# ems_mbed_rev_a.net
KiCad netlist of a schematic drawn in EAGLE
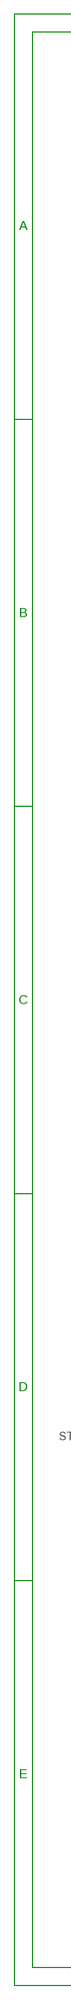
[diagram p0: schematic, sheet 1, part 1 of 2]
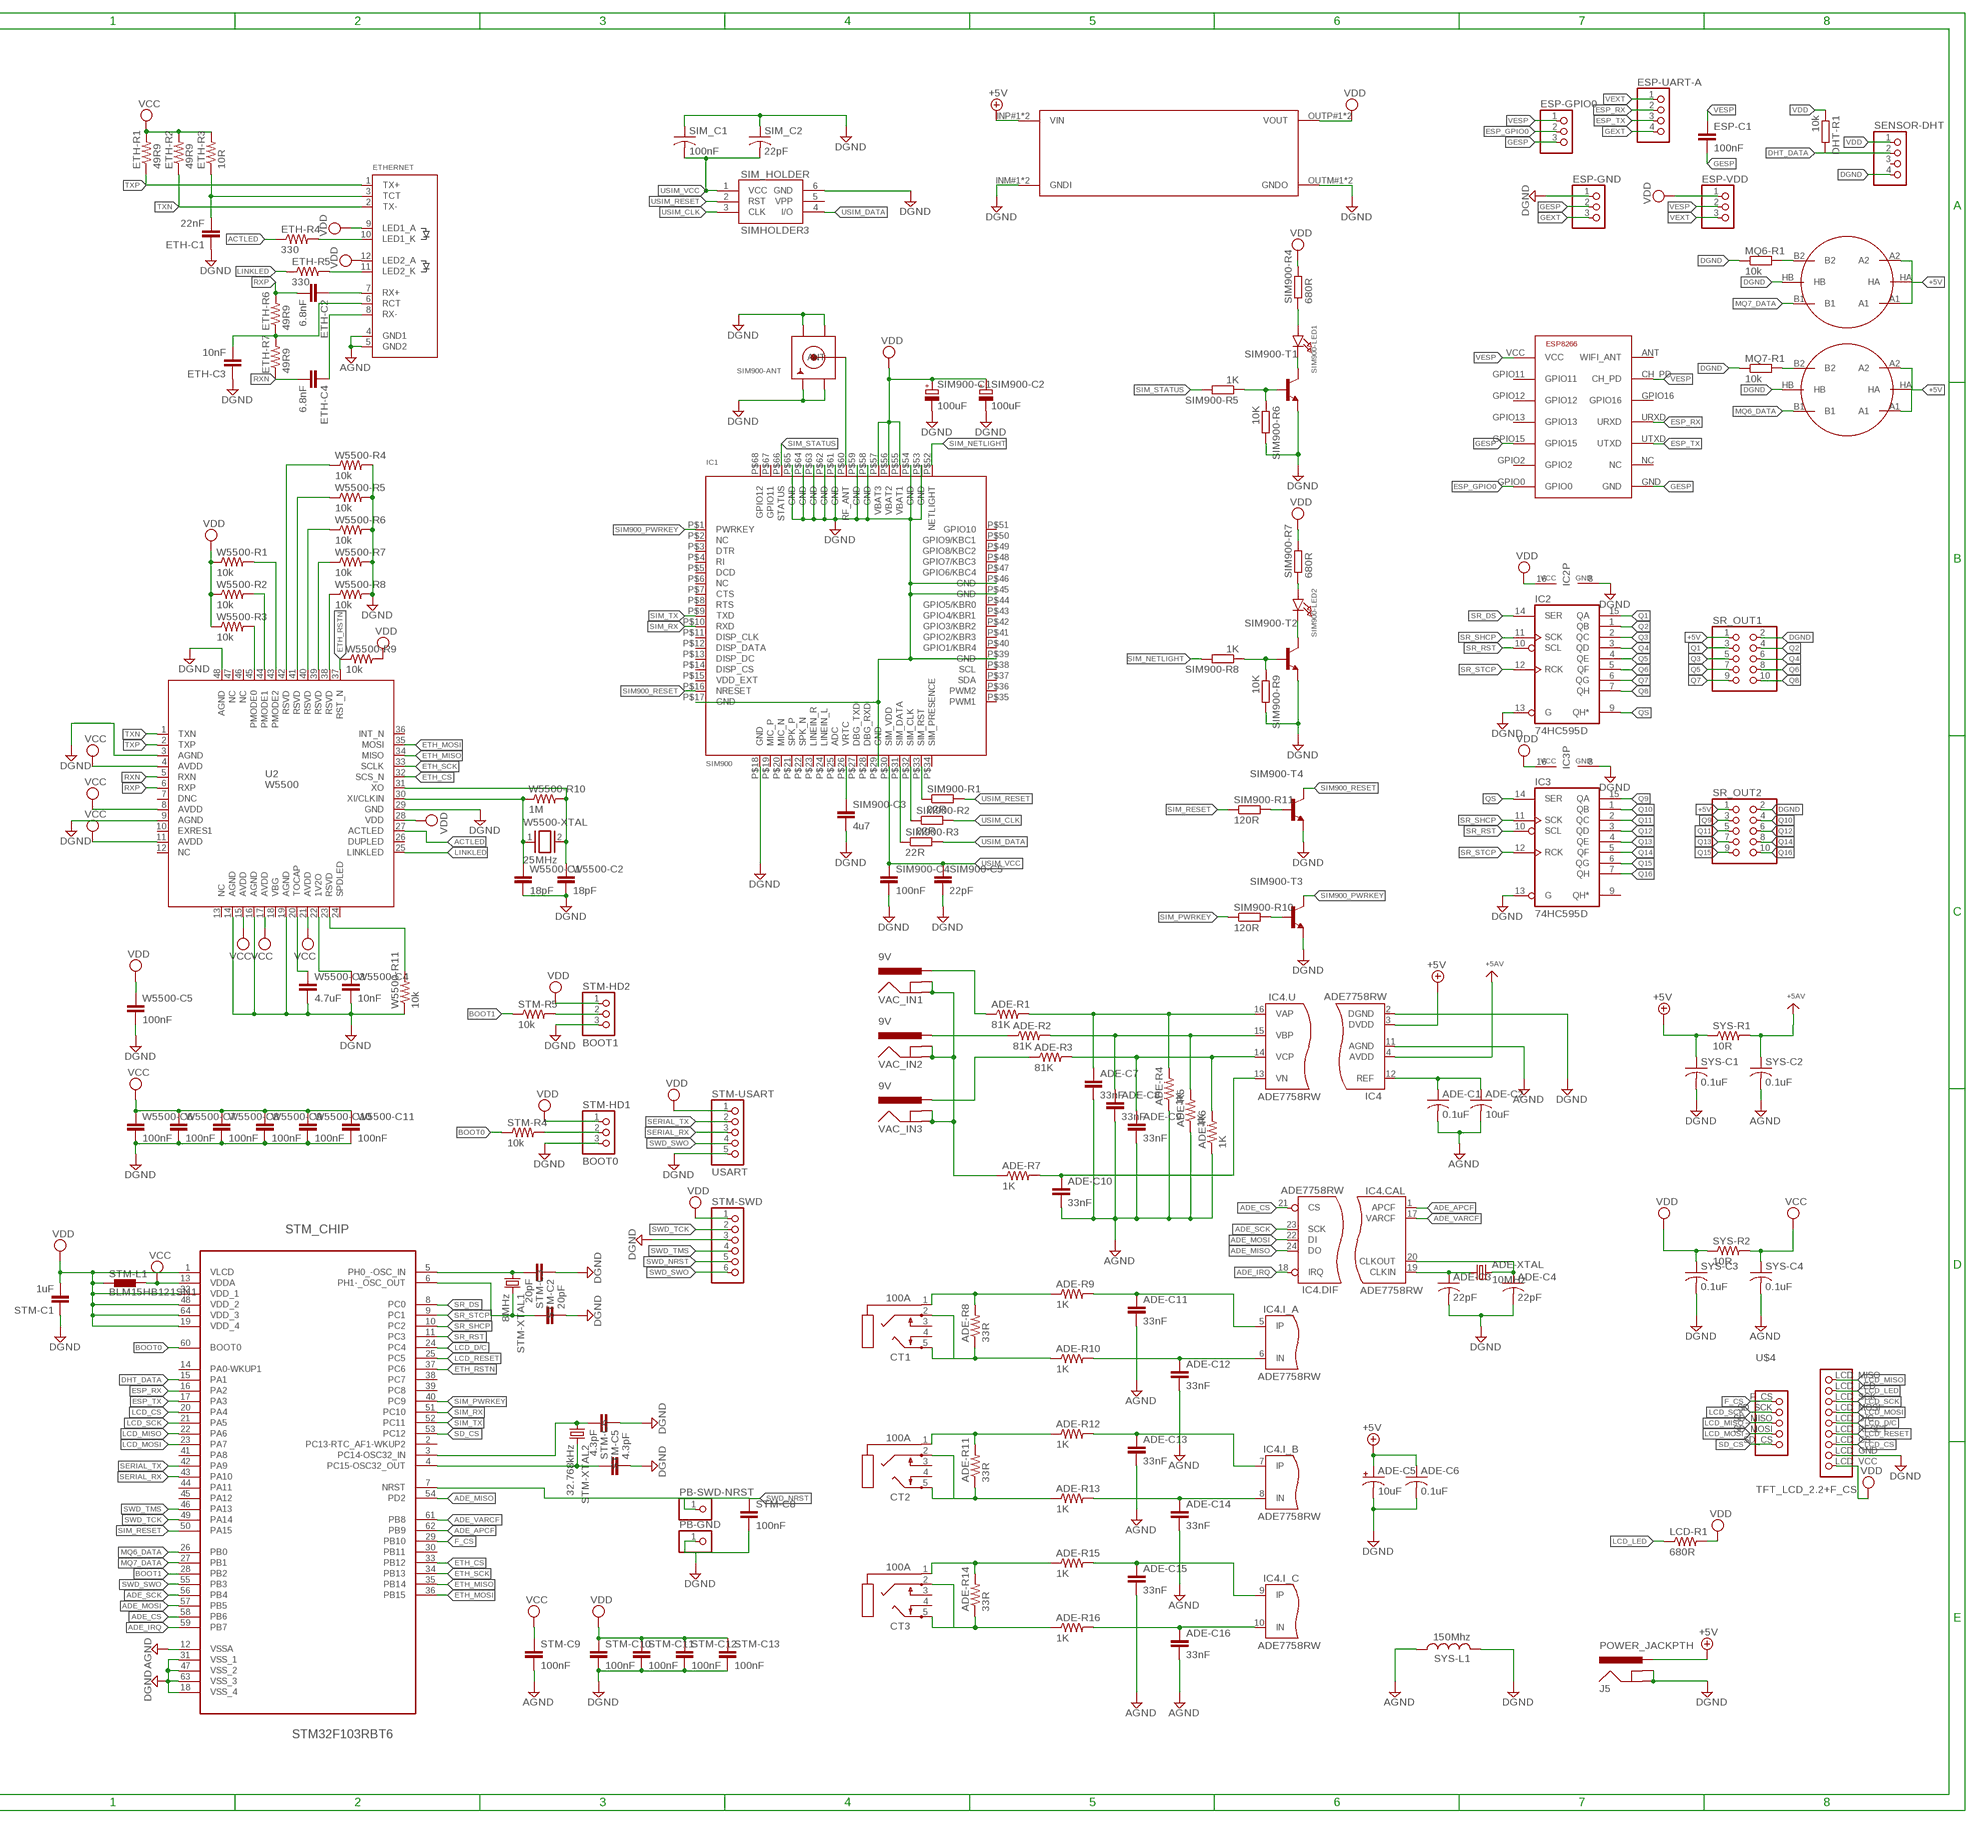
[diagram p1: schematic, sheet 1, part 2 of 2]

(export (version "E")
  (design (tool "Eeschema 10.0.6"))
  (components
    (comp (ref "ADE-C1")
      (value "0.1uF")
      (footprint "eagle-import:C0603@1")
      (libsource (lib "eagle-import") (part "C-USC0603"))
    )
    (comp (ref "ADE-C2")
      (value "10uF")
      (footprint "eagle-import:C0805K")
      (libsource (lib "eagle-import") (part "C-USC0805K"))
    )
    (comp (ref "ADE-C3")
      (value "22pF")
      (footprint "eagle-import:C0603@1")
      (libsource (lib "eagle-import") (part "C-USC0603"))
    )
    (comp (ref "ADE-C4")
      (value "22pF")
      (footprint "eagle-import:C0603")
      (libsource (lib "eagle-import") (part "resistor_C-USC0603"))
    )
    (comp (ref "ADE-C5")
      (value "10uF")
      (footprint "eagle-import:153CLV-0605")
      (libsource (lib "eagle-import") (part "CPOL-US153CLV-0605"))
    )
    (comp (ref "ADE-C6")
      (value "0.1uF")
      (footprint "eagle-import:C0603@1")
      (libsource (lib "eagle-import") (part "C-USC0603"))
    )
    (comp (ref "ADE-C7")
      (value "33nF")
      (footprint "eagle-import:0603-CAP")
      (libsource (lib "eagle-import") (part "CAP0603-CAP"))
    )
    (comp (ref "ADE-C8")
      (value "33nF")
      (footprint "eagle-import:0603-CAP")
      (libsource (lib "eagle-import") (part "CAP0603-CAP"))
    )
    (comp (ref "ADE-C9")
      (value "33nF")
      (footprint "eagle-import:0603-CAP")
      (libsource (lib "eagle-import") (part "CAP0603-CAP"))
    )
    (comp (ref "ADE-C10")
      (value "33nF")
      (footprint "eagle-import:0603-CAP")
      (libsource (lib "eagle-import") (part "CAP0603-CAP"))
    )
    (comp (ref "ADE-C11")
      (value "33nF")
      (footprint "eagle-import:0603-CAP")
      (libsource (lib "eagle-import") (part "CAP0603-CAP"))
    )
    (comp (ref "ADE-C12")
      (value "33nF")
      (footprint "eagle-import:0603-CAP")
      (libsource (lib "eagle-import") (part "CAP0603-CAP"))
    )
    (comp (ref "ADE-C13")
      (value "33nF")
      (footprint "eagle-import:0603-CAP")
      (libsource (lib "eagle-import") (part "CAP0603-CAP"))
    )
    (comp (ref "ADE-C14")
      (value "33nF")
      (footprint "eagle-import:0603-CAP")
      (libsource (lib "eagle-import") (part "CAP0603-CAP"))
    )
    (comp (ref "ADE-C15")
      (value "33nF")
      (footprint "eagle-import:0603-CAP")
      (libsource (lib "eagle-import") (part "CAP0603-CAP"))
    )
    (comp (ref "ADE-C16")
      (value "33nF")
      (footprint "eagle-import:0603-CAP")
      (libsource (lib "eagle-import") (part "CAP0603-CAP"))
    )
    (comp (ref "ADE-R1")
      (value "81K")
      (footprint "eagle-import:0603-RES")
      (libsource (lib "eagle-import") (part "RESISTOR0603-RES"))
    )
    (comp (ref "ADE-R2")
      (value "81K")
      (footprint "eagle-import:0603-RES")
      (libsource (lib "eagle-import") (part "RESISTOR0603-RES"))
    )
    (comp (ref "ADE-R3")
      (value "81K")
      (footprint "eagle-import:0603-RES")
      (libsource (lib "eagle-import") (part "RESISTOR0603-RES"))
    )
    (comp (ref "ADE-R4")
      (value "1K")
      (footprint "eagle-import:0603-RES")
      (libsource (lib "eagle-import") (part "RESISTOR0603-RES"))
    )
    (comp (ref "ADE-R5")
      (value "1K")
      (footprint "eagle-import:0603-RES")
      (libsource (lib "eagle-import") (part "RESISTOR0603-RES"))
    )
    (comp (ref "ADE-R6")
      (value "1K")
      (footprint "eagle-import:0603-RES")
      (libsource (lib "eagle-import") (part "RESISTOR0603-RES"))
    )
    (comp (ref "ADE-R7")
      (value "1K")
      (footprint "eagle-import:0603-RES")
      (libsource (lib "eagle-import") (part "RESISTOR0603-RES"))
    )
    (comp (ref "ADE-R8")
      (value "33R")
      (footprint "eagle-import:0603-RES")
      (libsource (lib "eagle-import") (part "RESISTOR0603-RES"))
    )
    (comp (ref "ADE-R9")
      (value "1K")
      (footprint "eagle-import:0603-RES")
      (libsource (lib "eagle-import") (part "RESISTOR0603-RES"))
    )
    (comp (ref "ADE-R10")
      (value "1K")
      (footprint "eagle-import:0603-RES")
      (libsource (lib "eagle-import") (part "RESISTOR0603-RES"))
    )
    (comp (ref "ADE-R11")
      (value "33R")
      (footprint "eagle-import:0603-RES")
      (libsource (lib "eagle-import") (part "RESISTOR0603-RES"))
    )
    (comp (ref "ADE-R12")
      (value "1K")
      (footprint "eagle-import:0603-RES")
      (libsource (lib "eagle-import") (part "RESISTOR0603-RES"))
    )
    (comp (ref "ADE-R13")
      (value "1K")
      (footprint "eagle-import:0603-RES")
      (libsource (lib "eagle-import") (part "RESISTOR0603-RES"))
    )
    (comp (ref "ADE-R14")
      (value "33R")
      (footprint "eagle-import:0603-RES")
      (libsource (lib "eagle-import") (part "RESISTOR0603-RES"))
    )
    (comp (ref "ADE-R15")
      (value "1K")
      (footprint "eagle-import:0603-RES")
      (libsource (lib "eagle-import") (part "RESISTOR0603-RES"))
    )
    (comp (ref "ADE-R16")
      (value "1K")
      (footprint "eagle-import:0603-RES")
      (libsource (lib "eagle-import") (part "RESISTOR0603-RES"))
    )
    (comp (ref "ADE-XTAL")
      (value "10MHz")
      (footprint "eagle-import:HC49US")
      (libsource (lib "eagle-import") (part "CRYSTALHC49US"))
    )
    (comp (ref "CT1")
      (value "100A")
      (footprint "eagle-import:STX3100")
      (libsource (lib "eagle-import") (part "AUDIO_STEREOJACK"))
    )
    (comp (ref "CT2")
      (value "100A")
      (footprint "eagle-import:STX3100")
      (libsource (lib "eagle-import") (part "AUDIO_STEREOJACK"))
    )
    (comp (ref "CT3")
      (value "100A")
      (footprint "eagle-import:STX3100")
      (libsource (lib "eagle-import") (part "AUDIO_STEREOJACK"))
    )
    (comp (ref "DCDC-3.5V")
      (value "DCDCMODULE_SMALL")
      (footprint "eagle-import:DCDCMODULE-SMALL")
      (libsource (lib "eagle-import") (part "DCDCMODULE_SMALL"))
    )
    (comp (ref "DHT-R1")
      (value "10k")
      (footprint "eagle-import:R0603")
      (libsource (lib "eagle-import") (part "resistor_R-EU_R0603"))
    )
    (comp (ref "ESP-C1")
      (value "100nF")
      (footprint "eagle-import:C0603@1")
      (libsource (lib "eagle-import") (part "C-EUC0603"))
    )
    (comp (ref "ESP-GND")
      (value "PINHD-1X3")
      (footprint "eagle-import:1X03")
      (libsource (lib "eagle-import") (part "PINHD-1X3"))
    )
    (comp (ref "ESP-GPIO0")
      (value "PINHD-1X3")
      (footprint "eagle-import:1X03")
      (libsource (lib "eagle-import") (part "PINHD-1X3"))
    )
    (comp (ref "ESP-UART-A")
      (value "PINHD-1X4")
      (footprint "eagle-import:1X04")
      (libsource (lib "eagle-import") (part "PINHD-1X4"))
    )
    (comp (ref "ESP-VDD")
      (value "PINHD-1X3")
      (footprint "eagle-import:1X03")
      (libsource (lib "eagle-import") (part "PINHD-1X3"))
    )
    (comp (ref "ESP8266")
      (value "ESP-07")
      (footprint "eagle-import:ESP-07")
      (libsource (lib "eagle-import") (part "ESP-07"))
    )
    (comp (ref "ETH-C1")
      (value "22nF")
      (footprint "eagle-import:C0603@1")
      (libsource (lib "eagle-import") (part "C-EUC0603"))
    )
    (comp (ref "ETH-C2")
      (value "6.8nF")
      (footprint "eagle-import:C0603@1")
      (libsource (lib "eagle-import") (part "C-EUC0603"))
    )
    (comp (ref "ETH-C3")
      (value "10nF")
      (footprint "eagle-import:C0603@1")
      (libsource (lib "eagle-import") (part "C-EUC0603"))
    )
    (comp (ref "ETH-C4")
      (value "6.8nF")
      (footprint "eagle-import:C0603@1")
      (libsource (lib "eagle-import") (part "C-EUC0603"))
    )
    (comp (ref "ETH-R1")
      (value "49R9")
      (footprint "eagle-import:R0603")
      (libsource (lib "eagle-import") (part "R-US_R0603"))
    )
    (comp (ref "ETH-R2")
      (value "49R9")
      (footprint "eagle-import:R0603")
      (libsource (lib "eagle-import") (part "R-US_R0603"))
    )
    (comp (ref "ETH-R3")
      (value "10R")
      (footprint "eagle-import:R0603")
      (libsource (lib "eagle-import") (part "R-US_R0603"))
    )
    (comp (ref "ETH-R4")
      (value "330")
      (footprint "eagle-import:R0603")
      (libsource (lib "eagle-import") (part "R-US_R0603"))
    )
    (comp (ref "ETH-R5")
      (value "330")
      (footprint "eagle-import:R0603")
      (libsource (lib "eagle-import") (part "R-US_R0603"))
    )
    (comp (ref "ETH-R6")
      (value "49R9")
      (footprint "eagle-import:R0603")
      (libsource (lib "eagle-import") (part "R-US_R0603"))
    )
    (comp (ref "ETH-R7")
      (value "49R9")
      (footprint "eagle-import:R0603")
      (libsource (lib "eagle-import") (part "R-US_R0603"))
    )
    (comp (ref "ETHERNET")
      (value "RJ45J0026D21BNL")
      (footprint "eagle-import:RJ45_PULSEJACK")
      (libsource (lib "eagle-import") (part "RJ45J0026D21BNL"))
    )
    (comp (ref "IC1")
      (value "SIM900")
      (footprint "eagle-import:SIM900_SMT")
      (libsource (lib "eagle-import") (part "GSM_SIM900_LITERAL"))
    )
    (comp (ref "IC2")
      (value "74HC595D")
      (footprint "eagle-import:SO16")
      (libsource (lib "eagle-import") (part "74595DHC"))
    )
    (comp (ref "IC3")
      (value "74HC595D")
      (footprint "eagle-import:SO16")
      (libsource (lib "eagle-import") (part "74595DHC"))
    )
    (comp (ref "IC4")
      (value "ADE7758RW")
      (footprint "eagle-import:SOIC24")
      (libsource (lib "eagle-import") (part "ADE7758RW"))
    )
    (comp (ref "J5")
      (value "POWER_JACKPTH")
      (footprint "eagle-import:POWER_JACK_PTH")
      (libsource (lib "eagle-import") (part "POWER_JACKPTH"))
    )
    (comp (ref "LCD-R1")
      (value "680R")
      (footprint "eagle-import:0603-RES")
      (libsource (lib "eagle-import") (part "RESISTOR0603-RES"))
    )
    (comp (ref "MQ6-R1")
      (value "10k")
      (footprint "eagle-import:R0603")
      (libsource (lib "eagle-import") (part "resistor_R-EU_R0603"))
    )
    (comp (ref "MQ7-R1")
      (value "10k")
      (footprint "eagle-import:R0603")
      (libsource (lib "eagle-import") (part "resistor_R-EU_R0603"))
    )
    (comp (ref "PB-GND")
      (value "PINHD-1X1CB")
      (footprint "eagle-import:1X01-CLEANBIG")
      (libsource (lib "eagle-import") (part "PINHD-1X1CB"))
    )
    (comp (ref "PB-SWD-NRST")
      (value "PINHD-1X1CB")
      (footprint "eagle-import:1X01-CLEANBIG")
      (libsource (lib "eagle-import") (part "PINHD-1X1CB"))
    )
    (comp (ref "SENSOR-DHT")
      (value "PINHD-1X4")
      (footprint "eagle-import:1X04")
      (libsource (lib "eagle-import") (part "PINHD-1X4"))
    )
    (comp (ref "SENSOR-MQ6")
      (value "METHANE_SENSOR")
      (footprint "eagle-import:MQ-3")
      (libsource (lib "eagle-import") (part "METHANE_SENSOR"))
    )
    (comp (ref "SENSOR-MQ7")
      (value "METHANE_SENSOR")
      (footprint "eagle-import:MQ-3")
      (libsource (lib "eagle-import") (part "METHANE_SENSOR"))
    )
    (comp (ref "SIM900-ANT")
      (value "SMACONNECTOR")
      (footprint "eagle-import:SMA90_DIP")
      (libsource (lib "eagle-import") (part "SMACONNECTOR"))
    )
    (comp (ref "SIM900-C1")
      (value "100uF")
      (footprint "eagle-import:153CLV-0605")
      (libsource (lib "eagle-import") (part "CPOL-EU153CLV-0605"))
    )
    (comp (ref "SIM900-C2")
      (value "100uF")
      (footprint "eagle-import:153CLV-0605")
      (libsource (lib "eagle-import") (part "CPOL-EU153CLV-0605"))
    )
    (comp (ref "SIM900-C3")
      (value "4u7")
      (footprint "eagle-import:C0603@1")
      (libsource (lib "eagle-import") (part "C-EUC0603"))
    )
    (comp (ref "SIM900-C4")
      (value "100nF")
      (footprint "eagle-import:C0603@1")
      (libsource (lib "eagle-import") (part "C-EUC0603"))
    )
    (comp (ref "SIM900-C5")
      (value "22pF")
      (footprint "eagle-import:C0603@1")
      (libsource (lib "eagle-import") (part "C-EUC0603"))
    )
    (comp (ref "SIM900-LED1")
      (value "LED0805_NOOUTLINE")
      (footprint "eagle-import:CHIPLED_0805_NOOUTLINE")
      (libsource (lib "eagle-import") (part "LED0805_NOOUTLINE"))
    )
    (comp (ref "SIM900-LED2")
      (value "LED0805_NOOUTLINE")
      (footprint "eagle-import:CHIPLED_0805_NOOUTLINE")
      (libsource (lib "eagle-import") (part "LED0805_NOOUTLINE"))
    )
    (comp (ref "SIM900-R1")
      (value "22R")
      (footprint "eagle-import:R0603")
      (libsource (lib "eagle-import") (part "R-EU_R0603"))
    )
    (comp (ref "SIM900-R2")
      (value "22R")
      (footprint "eagle-import:R0603")
      (libsource (lib "eagle-import") (part "R-EU_R0603"))
    )
    (comp (ref "SIM900-R3")
      (value "22R")
      (footprint "eagle-import:R0603")
      (libsource (lib "eagle-import") (part "R-EU_R0603"))
    )
    (comp (ref "SIM900-R4")
      (value "680R")
      (footprint "eagle-import:R0603")
      (libsource (lib "eagle-import") (part "R-EU_R0603"))
    )
    (comp (ref "SIM900-R5")
      (value "1K")
      (footprint "eagle-import:R0603")
      (libsource (lib "eagle-import") (part "R-EU_R0603"))
    )
    (comp (ref "SIM900-R6")
      (value "10K")
      (footprint "eagle-import:R0603")
      (libsource (lib "eagle-import") (part "R-EU_R0603"))
    )
    (comp (ref "SIM900-R7")
      (value "680R")
      (footprint "eagle-import:R0603")
      (libsource (lib "eagle-import") (part "R-EU_R0603"))
    )
    (comp (ref "SIM900-R8")
      (value "1K")
      (footprint "eagle-import:R0603")
      (libsource (lib "eagle-import") (part "R-EU_R0603"))
    )
    (comp (ref "SIM900-R9")
      (value "10K")
      (footprint "eagle-import:R0603")
      (libsource (lib "eagle-import") (part "R-EU_R0603"))
    )
    (comp (ref "SIM900-R10")
      (value "120R")
      (footprint "eagle-import:R0603")
      (libsource (lib "eagle-import") (part "resistor_R-EU_R0603"))
    )
    (comp (ref "SIM900-R11")
      (value "120R")
      (footprint "eagle-import:R0603")
      (libsource (lib "eagle-import") (part "resistor_R-EU_R0603"))
    )
    (comp (ref "SIM900-T1")
      (value "MMBT2222ALT1-NPN-SOT23-BEC")
      (footprint "eagle-import:SOT23-BEC")
      (libsource (lib "eagle-import") (part "-NPN-SOT23-BECMMBT2222ALT1"))
    )
    (comp (ref "SIM900-T2")
      (value "MMBT2222ALT1-NPN-SOT23-BEC")
      (footprint "eagle-import:SOT23-BEC")
      (libsource (lib "eagle-import") (part "-NPN-SOT23-BECMMBT2222ALT1"))
    )
    (comp (ref "SIM900-T3")
      (value "MMBT2222ALT1-NPN-SOT23-BEC")
      (footprint "eagle-import:SOT23-BEC")
      (libsource (lib "eagle-import") (part "transistor-neu-to92_-NPN-SOT23-BECMMBT2222ALT1"))
    )
    (comp (ref "SIM900-T4")
      (value "MMBT2222ALT1-NPN-SOT23-BEC")
      (footprint "eagle-import:SOT23-BEC")
      (libsource (lib "eagle-import") (part "transistor-neu-to92_-NPN-SOT23-BECMMBT2222ALT1"))
    )
    (comp (ref "SIM_C1")
      (value "100nF")
      (footprint "eagle-import:C0603K")
      (libsource (lib "eagle-import") (part "C-USC0603K"))
    )
    (comp (ref "SIM_C2")
      (value "22pF")
      (footprint "eagle-import:C0603K")
      (libsource (lib "eagle-import") (part "C-USC0603K"))
    )
    (comp (ref "SIM_HOLDER")
      (value "SIMHOLDER3")
      (footprint "eagle-import:SIMHOLDER3")
      (libsource (lib "eagle-import") (part "SIMHOLDER3"))
    )
    (comp (ref "SR_OUT1")
      (value "PINHD-2X5/90")
      (footprint "eagle-import:2X05_90")
      (libsource (lib "eagle-import") (part "PINHD-2X5/90"))
    )
    (comp (ref "SR_OUT2")
      (value "PINHD-2X5/90")
      (footprint "eagle-import:2X05_90")
      (libsource (lib "eagle-import") (part "PINHD-2X5/90"))
    )
    (comp (ref "STM-C1")
      (value "1uF")
      (footprint "eagle-import:C0603@1")
      (libsource (lib "eagle-import") (part "C-EUC0603"))
    )
    (comp (ref "STM-C2")
      (value "20pF")
      (footprint "eagle-import:C0603@1")
      (libsource (lib "eagle-import") (part "C-EUC0603"))
    )
    (comp (ref "STM-C3")
      (value "20pF")
      (footprint "eagle-import:C0603@1")
      (libsource (lib "eagle-import") (part "C-EUC0603"))
    )
    (comp (ref "STM-C5")
      (value "4.3pF")
      (footprint "eagle-import:C0603@1")
      (libsource (lib "eagle-import") (part "C-EUC0603"))
    )
    (comp (ref "STM-C6")
      (value "4.3pF")
      (footprint "eagle-import:C0603@1")
      (libsource (lib "eagle-import") (part "C-EUC0603"))
    )
    (comp (ref "STM-C8")
      (value "100nF")
      (footprint "eagle-import:C0603@1")
      (libsource (lib "eagle-import") (part "C-EUC0603"))
    )
    (comp (ref "STM-C9")
      (value "100nF")
      (footprint "eagle-import:C0603@1")
      (libsource (lib "eagle-import") (part "C-EUC0603"))
    )
    (comp (ref "STM-C10")
      (value "100nF")
      (footprint "eagle-import:C0603@1")
      (libsource (lib "eagle-import") (part "C-EUC0603"))
    )
    (comp (ref "STM-C11")
      (value "100nF")
      (footprint "eagle-import:C0603@1")
      (libsource (lib "eagle-import") (part "C-EUC0603"))
    )
    (comp (ref "STM-C12")
      (value "100nF")
      (footprint "eagle-import:C0603@1")
      (libsource (lib "eagle-import") (part "C-EUC0603"))
    )
    (comp (ref "STM-C13")
      (value "100nF")
      (footprint "eagle-import:C0603@1")
      (libsource (lib "eagle-import") (part "C-EUC0603"))
    )
    (comp (ref "STM-HD1")
      (value "BOOT0")
      (footprint "eagle-import:1X03")
      (libsource (lib "eagle-import") (part "PINHD-1X3"))
    )
    (comp (ref "STM-HD2")
      (value "BOOT1")
      (footprint "eagle-import:1X03")
      (libsource (lib "eagle-import") (part "PINHD-1X3"))
    )
    (comp (ref "STM-L1")
      (value "BLM15HB121SN1")
      (footprint "eagle-import:0402")
      (libsource (lib "eagle-import") (part "BLM15HB121SN1"))
    )
    (comp (ref "STM-R4")
      (value "10k")
      (footprint "eagle-import:R0603")
      (libsource (lib "eagle-import") (part "R-US_R0603"))
    )
    (comp (ref "STM-R5")
      (value "10k")
      (footprint "eagle-import:R0603")
      (libsource (lib "eagle-import") (part "R-US_R0603"))
    )
    (comp (ref "STM-SWD")
      (value "PINHD-1X6")
      (footprint "eagle-import:1X06")
      (libsource (lib "eagle-import") (part "PINHD-1X6"))
    )
    (comp (ref "STM-USART")
      (value "USART")
      (footprint "eagle-import:PINHD5")
      (libsource (lib "eagle-import") (part "PINHD5"))
    )
    (comp (ref "STM-XTAL1")
      (value "8MHz")
      (footprint "eagle-import:TC26H")
      (libsource (lib "eagle-import") (part "CRYSTALTC26H"))
    )
    (comp (ref "STM-XTAL2")
      (value "32.768kHz")
      (footprint "eagle-import:TC26H")
      (libsource (lib "eagle-import") (part "CRYSTALTC26H"))
    )
    (comp (ref "STM_CHIP")
      (value "STM32F103RBT6")
      (footprint "eagle-import:QFP50P1200X1200X160-64N")
      (fields (field (name "MPN") "STM32L152RBT6"))
      (libsource (lib "eagle-import") (part "STM32L152RBT6"))
    )
    (comp (ref "SYS-C1")
      (value "0.1uF")
      (footprint "eagle-import:C0603@1")
      (libsource (lib "eagle-import") (part "C-USC0603"))
    )
    (comp (ref "SYS-C2")
      (value "0.1uF")
      (footprint "eagle-import:C0603@1")
      (libsource (lib "eagle-import") (part "C-USC0603"))
    )
    (comp (ref "SYS-C3")
      (value "0.1uF")
      (footprint "eagle-import:C0603@1")
      (libsource (lib "eagle-import") (part "C-USC0603"))
    )
    (comp (ref "SYS-C4")
      (value "0.1uF")
      (footprint "eagle-import:C0603@1")
      (libsource (lib "eagle-import") (part "C-USC0603"))
    )
    (comp (ref "SYS-L1")
      (value "150Mhz")
      (footprint "eagle-import:POWER-CHOKE_WE-TPC")
      (libsource (lib "eagle-import") (part "L-USWE-TPC"))
    )
    (comp (ref "SYS-R1")
      (value "10R")
      (footprint "eagle-import:0603-RES")
      (libsource (lib "eagle-import") (part "RESISTOR0603-RES"))
    )
    (comp (ref "SYS-R2")
      (value "10R")
      (footprint "eagle-import:0603-RES")
      (libsource (lib "eagle-import") (part "RESISTOR0603-RES"))
    )
    (comp (ref "U$4")
      (value "TFT_LCD_2.2+F_CS")
      (footprint "eagle-import:TFT_LCD_2.2+F_CS")
      (libsource (lib "eagle-import") (part "TFT_LCD_2.2+F_CS"))
    )
    (comp (ref "U2")
      (value "W5500")
      (footprint "eagle-import:W5500")
      (libsource (lib "eagle-import") (part "W5500"))
    )
    (comp (ref "VAC_IN1")
      (value "9V")
      (footprint "eagle-import:POWER_JACK_PTH")
      (libsource (lib "eagle-import") (part "POWER_JACKPTH"))
    )
    (comp (ref "VAC_IN2")
      (value "9V")
      (footprint "eagle-import:POWER_JACK_PTH")
      (libsource (lib "eagle-import") (part "POWER_JACKPTH"))
    )
    (comp (ref "VAC_IN3")
      (value "9V")
      (footprint "eagle-import:POWER_JACK_PTH")
      (libsource (lib "eagle-import") (part "POWER_JACKPTH"))
    )
    (comp (ref "W5500-C1")
      (value "18pF")
      (footprint "eagle-import:C0603@1")
      (libsource (lib "eagle-import") (part "C-EUC0603"))
    )
    (comp (ref "W5500-C2")
      (value "18pF")
      (footprint "eagle-import:C0603@1")
      (libsource (lib "eagle-import") (part "C-EUC0603"))
    )
    (comp (ref "W5500-C3")
      (value "4.7uF")
      (footprint "eagle-import:C0603@1")
      (libsource (lib "eagle-import") (part "C-EUC0603"))
    )
    (comp (ref "W5500-C4")
      (value "10nF")
      (footprint "eagle-import:C0603@1")
      (libsource (lib "eagle-import") (part "C-EUC0603"))
    )
    (comp (ref "W5500-C5")
      (value "100nF")
      (footprint "eagle-import:C0603@1")
      (libsource (lib "eagle-import") (part "C-EUC0603"))
    )
    (comp (ref "W5500-C6")
      (value "100nF")
      (footprint "eagle-import:C0603@1")
      (libsource (lib "eagle-import") (part "C-EUC0603"))
    )
    (comp (ref "W5500-C7")
      (value "100nF")
      (footprint "eagle-import:C0603@1")
      (libsource (lib "eagle-import") (part "C-EUC0603"))
    )
    (comp (ref "W5500-C8")
      (value "100nF")
      (footprint "eagle-import:C0603@1")
      (libsource (lib "eagle-import") (part "C-EUC0603"))
    )
    (comp (ref "W5500-C9")
      (value "100nF")
      (footprint "eagle-import:C0603@1")
      (libsource (lib "eagle-import") (part "C-EUC0603"))
    )
    (comp (ref "W5500-C10")
      (value "100nF")
      (footprint "eagle-import:C0603@1")
      (libsource (lib "eagle-import") (part "C-EUC0603"))
    )
    (comp (ref "W5500-C11")
      (value "100nF")
      (footprint "eagle-import:C0603@1")
      (libsource (lib "eagle-import") (part "C-EUC0603"))
    )
    (comp (ref "W5500-R1")
      (value "10k")
      (footprint "eagle-import:R0603")
      (libsource (lib "eagle-import") (part "R-US_R0603"))
    )
    (comp (ref "W5500-R2")
      (value "10k")
      (footprint "eagle-import:R0603")
      (libsource (lib "eagle-import") (part "R-US_R0603"))
    )
    (comp (ref "W5500-R3")
      (value "10k")
      (footprint "eagle-import:R0603")
      (libsource (lib "eagle-import") (part "R-US_R0603"))
    )
    (comp (ref "W5500-R4")
      (value "10k")
      (footprint "eagle-import:R0603")
      (libsource (lib "eagle-import") (part "R-US_R0603"))
    )
    (comp (ref "W5500-R5")
      (value "10k")
      (footprint "eagle-import:R0603")
      (libsource (lib "eagle-import") (part "R-US_R0603"))
    )
    (comp (ref "W5500-R6")
      (value "10k")
      (footprint "eagle-import:R0603")
      (libsource (lib "eagle-import") (part "R-US_R0603"))
    )
    (comp (ref "W5500-R7")
      (value "10k")
      (footprint "eagle-import:R0603")
      (libsource (lib "eagle-import") (part "R-US_R0603"))
    )
    (comp (ref "W5500-R8")
      (value "10k")
      (footprint "eagle-import:R0603")
      (libsource (lib "eagle-import") (part "R-US_R0603"))
    )
    (comp (ref "W5500-R9")
      (value "10k")
      (footprint "eagle-import:R0603")
      (libsource (lib "eagle-import") (part "R-US_R0603"))
    )
    (comp (ref "W5500-R10")
      (value "1M")
      (footprint "eagle-import:R0603")
      (libsource (lib "eagle-import") (part "R-US_R0603"))
    )
    (comp (ref "W5500-R11")
      (value "10k")
      (footprint "eagle-import:R0603")
      (libsource (lib "eagle-import") (part "R-US_R0603"))
    )
    (comp (ref "W5500-XTAL")
      (value "25MHz")
      (footprint "eagle-import:QS")
      (libsource (lib "eagle-import") (part "XTAL/S"))
    )
  )
  (nets
    (net (code "1") (name "+5AV") (class "Default")
      (node (ref "IC4") (pin "4") (pinfunction "AVDD_4") (pintype "power_in"))
      (node (ref "SYS-C2") (pin "1") (pinfunction "1_1") (pintype "passive"))
      (node (ref "SYS-R1") (pin "2") (pinfunction "2_2") (pintype "passive"))
    )
    (net (code "2") (name "+5V") (class "Default")
      (node (ref "ADE-C5") (pin "+") (pinfunction "+_+") (pintype "passive"))
      (node (ref "ADE-C6") (pin "1") (pinfunction "1_1") (pintype "passive"))
      (node (ref "DCDC-3.5V") (pin "INP#1") (pinfunction "VIN_INP#1") (pintype "bidirectional"))
      (node (ref "DCDC-3.5V") (pin "INP#2") (pinfunction "VIN_INP#2") (pintype "bidirectional"))
      (node (ref "IC4") (pin "3") (pinfunction "DVDD_3") (pintype "power_in"))
      (node (ref "J5") (pin "PWR") (pinfunction "PWR_PWR") (pintype "bidirectional"))
      (node (ref "SENSOR-MQ6") (pin "A1") (pinfunction "A1_A1") (pintype "bidirectional"))
      (node (ref "SENSOR-MQ6") (pin "A2") (pinfunction "A2_A2") (pintype "bidirectional"))
      (node (ref "SENSOR-MQ6") (pin "HA") (pinfunction "HA_HA") (pintype "bidirectional"))
      (node (ref "SENSOR-MQ7") (pin "A1") (pinfunction "A1_A1") (pintype "bidirectional"))
      (node (ref "SENSOR-MQ7") (pin "A2") (pinfunction "A2_A2") (pintype "bidirectional"))
      (node (ref "SENSOR-MQ7") (pin "HA") (pinfunction "HA_HA") (pintype "bidirectional"))
      (node (ref "SR_OUT1") (pin "1") (pinfunction "1_1") (pintype "passive"))
      (node (ref "SR_OUT2") (pin "1") (pinfunction "1_1") (pintype "passive"))
      (node (ref "SYS-C1") (pin "1") (pinfunction "1_1") (pintype "passive"))
      (node (ref "SYS-R1") (pin "1") (pinfunction "1_1") (pintype "passive"))
    )
    (net (code "3") (name "/GPIO11") (class "Default")
      (node (ref "IC1") (pin "P$67") (pinfunction "GPIO11_P$67") (pintype "power_in"))
    )
    (net (code "4") (name "/GPIO12") (class "Default")
      (node (ref "IC1") (pin "P$68") (pinfunction "GPIO12_P$68") (pintype "power_in"))
    )
    (net (code "5") (name "ACTLED") (class "Default")
      (node (ref "ETH-R4") (pin "1") (pinfunction "1_1") (pintype "passive"))
      (node (ref "U2") (pin "27") (pinfunction "ACTLED_27") (pintype "passive"))
    )
    (net (code "6") (name "ADE_APCF") (class "Default")
      (node (ref "IC4") (pin "1") (pinfunction "APCF_1") (pintype "output"))
      (node (ref "STM_CHIP") (pin "62") (pinfunction "PB9_62") (pintype "bidirectional"))
    )
    (net (code "7") (name "ADE_CS") (class "Default")
      (node (ref "IC4") (pin "21") (pinfunction "CS_21") (pintype "input"))
      (node (ref "STM_CHIP") (pin "58") (pinfunction "PB6_58") (pintype "bidirectional"))
    )
    (net (code "8") (name "ADE_IRQ") (class "Default")
      (node (ref "IC4") (pin "18") (pinfunction "IRQ_18") (pintype "output"))
      (node (ref "STM_CHIP") (pin "59") (pinfunction "PB7_59") (pintype "bidirectional"))
    )
    (net (code "9") (name "ADE_MISO") (class "Default")
      (node (ref "IC4") (pin "24") (pinfunction "DO_24") (pintype "output"))
      (node (ref "STM_CHIP") (pin "54") (pinfunction "PD2_54") (pintype "bidirectional"))
    )
    (net (code "10") (name "ADE_MOSI") (class "Default")
      (node (ref "IC4") (pin "22") (pinfunction "DI_22") (pintype "input"))
      (node (ref "STM_CHIP") (pin "57") (pinfunction "PB5_57") (pintype "bidirectional"))
    )
    (net (code "11") (name "ADE_SCK") (class "Default")
      (node (ref "IC4") (pin "23") (pinfunction "SCK_23") (pintype "input"))
      (node (ref "STM_CHIP") (pin "56") (pinfunction "PB4_56") (pintype "bidirectional"))
    )
    (net (code "12") (name "ADE_VARCF") (class "Default")
      (node (ref "IC4") (pin "17") (pinfunction "VARCF_17") (pintype "output"))
      (node (ref "STM_CHIP") (pin "61") (pinfunction "PB8_61") (pintype "bidirectional"))
    )
    (net (code "13") (name "AGND") (class "Default")
      (node (ref "ADE-C1") (pin "2") (pinfunction "2_2") (pintype "passive"))
      (node (ref "ADE-C10") (pin "2") (pinfunction "2_2") (pintype "passive"))
      (node (ref "ADE-C11") (pin "2") (pinfunction "2_2") (pintype "passive"))
      (node (ref "ADE-C12") (pin "2") (pinfunction "2_2") (pintype "passive"))
      (node (ref "ADE-C13") (pin "2") (pinfunction "2_2") (pintype "passive"))
      (node (ref "ADE-C14") (pin "2") (pinfunction "2_2") (pintype "passive"))
      (node (ref "ADE-C15") (pin "2") (pinfunction "2_2") (pintype "passive"))
      (node (ref "ADE-C16") (pin "2") (pinfunction "2_2") (pintype "passive"))
      (node (ref "ADE-C2") (pin "2") (pinfunction "2_2") (pintype "passive"))
      (node (ref "ADE-C7") (pin "2") (pinfunction "2_2") (pintype "passive"))
      (node (ref "ADE-C8") (pin "2") (pinfunction "2_2") (pintype "passive"))
      (node (ref "ADE-C9") (pin "2") (pinfunction "2_2") (pintype "passive"))
      (node (ref "ADE-R4") (pin "1") (pinfunction "1_1") (pintype "passive"))
      (node (ref "ADE-R5") (pin "1") (pinfunction "1_1") (pintype "passive"))
      (node (ref "ADE-R6") (pin "1") (pinfunction "1_1") (pintype "passive"))
      (node (ref "ETHERNET") (pin "4") (pinfunction "GND1_4") (pintype "bidirectional"))
      (node (ref "ETHERNET") (pin "5") (pinfunction "GND2_5") (pintype "bidirectional"))
      (node (ref "IC4") (pin "11") (pinfunction "AGND_11") (pintype "power_in"))
      (node (ref "STM-C9") (pin "2") (pinfunction "2_2") (pintype "passive"))
      (node (ref "STM_CHIP") (pin "12") (pinfunction "VSSA_12") (pintype "power_in"))
      (node (ref "SYS-C2") (pin "2") (pinfunction "2_2") (pintype "passive"))
      (node (ref "SYS-C4") (pin "2") (pinfunction "2_2") (pintype "passive"))
      (node (ref "SYS-L1") (pin "1") (pinfunction "1_1") (pintype "passive"))
    )
    (net (code "14") (name "BOOT0") (class "Default")
      (node (ref "STM-R4") (pin "1") (pinfunction "1_1") (pintype "passive"))
      (node (ref "STM_CHIP") (pin "60") (pinfunction "BOOT0_60") (pintype "input"))
    )
    (net (code "15") (name "BOOT1") (class "Default")
      (node (ref "STM-R5") (pin "1") (pinfunction "1_1") (pintype "passive"))
      (node (ref "STM_CHIP") (pin "28") (pinfunction "PB2_28") (pintype "bidirectional"))
    )
    (net (code "16") (name "DGND") (class "Default")
      (node (ref "ADE-C3") (pin "2") (pinfunction "2_2") (pintype "passive"))
      (node (ref "ADE-C4") (pin "2") (pinfunction "2_2") (pintype "passive"))
      (node (ref "ADE-C5") (pin "-") (pinfunction "-_-") (pintype "passive"))
      (node (ref "ADE-C6") (pin "2") (pinfunction "2_2") (pintype "passive"))
      (node (ref "DCDC-3.5V") (pin "INM#1") (pinfunction "GNDI_INM#1") (pintype "bidirectional"))
      (node (ref "DCDC-3.5V") (pin "INM#2") (pinfunction "GNDI_INM#2") (pintype "bidirectional"))
      (node (ref "DCDC-3.5V") (pin "OUTM#1") (pinfunction "GNDO_OUTM#1") (pintype "bidirectional"))
      (node (ref "DCDC-3.5V") (pin "OUTM#2") (pinfunction "GNDO_OUTM#2") (pintype "bidirectional"))
      (node (ref "ESP-GND") (pin "1") (pinfunction "1_1") (pintype "passive"))
      (node (ref "ETH-C1") (pin "1") (pinfunction "1_1") (pintype "passive"))
      (node (ref "ETH-C3") (pin "1") (pinfunction "1_1") (pintype "passive"))
      (node (ref "IC1") (pin "P$17") (pinfunction "GND_P$17") (pintype "power_in"))
      (node (ref "IC1") (pin "P$18") (pinfunction "GND_P$18") (pintype "power_in"))
      (node (ref "IC1") (pin "P$29") (pinfunction "GND_P$29") (pintype "power_in"))
      (node (ref "IC1") (pin "P$39") (pinfunction "GND_P$39") (pintype "power_in"))
      (node (ref "IC1") (pin "P$45") (pinfunction "GND_P$45") (pintype "power_in"))
      (node (ref "IC1") (pin "P$46") (pinfunction "GND_P$46") (pintype "power_in"))
      (node (ref "IC1") (pin "P$53") (pinfunction "GND_P$53") (pintype "power_in"))
      (node (ref "IC1") (pin "P$54") (pinfunction "GND_P$54") (pintype "power_in"))
      (node (ref "IC1") (pin "P$58") (pinfunction "GND_P$58") (pintype "power_in"))
      (node (ref "IC1") (pin "P$59") (pinfunction "GND_P$59") (pintype "power_in"))
      (node (ref "IC1") (pin "P$61") (pinfunction "GND_P$61") (pintype "power_in"))
      (node (ref "IC1") (pin "P$62") (pinfunction "GND_P$62") (pintype "power_in"))
      (node (ref "IC1") (pin "P$63") (pinfunction "GND_P$63") (pintype "power_in"))
      (node (ref "IC1") (pin "P$64") (pinfunction "GND_P$64") (pintype "power_in"))
      (node (ref "IC1") (pin "P$65") (pinfunction "GND_P$65") (pintype "power_in"))
      (node (ref "IC2") (pin "13") (pinfunction "G_13") (pintype "input"))
      (node (ref "IC2") (pin "8") (pinfunction "GND_8") (pintype "power_in"))
      (node (ref "IC3") (pin "13") (pinfunction "G_13") (pintype "input"))
      (node (ref "IC3") (pin "8") (pinfunction "GND_8") (pintype "power_in"))
      (node (ref "IC4") (pin "2") (pinfunction "DGND_2") (pintype "power_in"))
      (node (ref "J5") (pin "GND") (pinfunction "GND_GND") (pintype "bidirectional"))
      (node (ref "J5") (pin "GNDBREAK") (pinfunction "GNDBREAK_GNDBREAK") (pintype "bidirectional"))
      (node (ref "MQ6-R1") (pin "1") (pinfunction "1_1") (pintype "passive"))
      (node (ref "MQ7-R1") (pin "1") (pinfunction "1_1") (pintype "passive"))
      (node (ref "PB-GND") (pin "1") (pinfunction "1_1") (pintype "passive"))
      (node (ref "SENSOR-DHT") (pin "4") (pinfunction "4_4") (pintype "passive"))
      (node (ref "SENSOR-MQ6") (pin "HB") (pinfunction "HB_HB") (pintype "bidirectional"))
      (node (ref "SENSOR-MQ7") (pin "HB") (pinfunction "HB_HB") (pintype "bidirectional"))
      (node (ref "SIM900-ANT") (pin "GND1") (pinfunction "GND1_GND1") (pintype "power_in"))
      (node (ref "SIM900-ANT") (pin "GND2") (pinfunction "GND2_GND2") (pintype "power_in"))
      (node (ref "SIM900-ANT") (pin "GND3") (pinfunction "GND3_GND3") (pintype "power_in"))
      (node (ref "SIM900-ANT") (pin "GND4") (pinfunction "GND4_GND4") (pintype "power_in"))
      (node (ref "SIM900-C1") (pin "-") (pinfunction "-_-") (pintype "passive"))
      (node (ref "SIM900-C2") (pin "-") (pinfunction "-_-") (pintype "passive"))
      (node (ref "SIM900-C3") (pin "2") (pinfunction "2_2") (pintype "passive"))
      (node (ref "SIM900-C4") (pin "2") (pinfunction "2_2") (pintype "passive"))
      (node (ref "SIM900-C5") (pin "2") (pinfunction "2_2") (pintype "passive"))
      (node (ref "SIM900-R6") (pin "2") (pinfunction "2_2") (pintype "passive"))
      (node (ref "SIM900-R9") (pin "2") (pinfunction "2_2") (pintype "passive"))
      (node (ref "SIM900-T1") (pin "E") (pinfunction "E_E") (pintype "passive"))
      (node (ref "SIM900-T2") (pin "E") (pinfunction "E_E") (pintype "passive"))
      (node (ref "SIM900-T3") (pin "E") (pinfunction "E_E") (pintype "passive"))
      (node (ref "SIM900-T4") (pin "E") (pinfunction "E_E") (pintype "passive"))
      (node (ref "SIM_C1") (pin "1") (pinfunction "1_1") (pintype "passive"))
      (node (ref "SIM_C2") (pin "1") (pinfunction "1_1") (pintype "passive"))
      (node (ref "SIM_HOLDER") (pin "6") (pinfunction "GND_6") (pintype "bidirectional"))
      (node (ref "SR_OUT1") (pin "2") (pinfunction "2_2") (pintype "passive"))
      (node (ref "SR_OUT2") (pin "2") (pinfunction "2_2") (pintype "passive"))
      (node (ref "STM-C1") (pin "1") (pinfunction "1_1") (pintype "passive"))
      (node (ref "STM-C10") (pin "2") (pinfunction "2_2") (pintype "passive"))
      (node (ref "STM-C11") (pin "2") (pinfunction "2_2") (pintype "passive"))
      (node (ref "STM-C12") (pin "2") (pinfunction "2_2") (pintype "passive"))
      (node (ref "STM-C13") (pin "2") (pinfunction "2_2") (pintype "passive"))
      (node (ref "STM-C2") (pin "1") (pinfunction "1_1") (pintype "passive"))
      (node (ref "STM-C3") (pin "2") (pinfunction "2_2") (pintype "passive"))
      (node (ref "STM-C5") (pin "1") (pinfunction "1_1") (pintype "passive"))
      (node (ref "STM-C6") (pin "2") (pinfunction "2_2") (pintype "passive"))
      (node (ref "STM-C8") (pin "2") (pinfunction "2_2") (pintype "passive"))
      (node (ref "STM-HD1") (pin "3") (pinfunction "3_3") (pintype "passive"))
      (node (ref "STM-HD2") (pin "3") (pinfunction "3_3") (pintype "passive"))
      (node (ref "STM-SWD") (pin "3") (pinfunction "3_3") (pintype "passive"))
      (node (ref "STM-USART") (pin "5") (pinfunction "5_5") (pintype "passive"))
      (node (ref "STM_CHIP") (pin "18") (pinfunction "VSS_4_18") (pintype "power_in"))
      (node (ref "STM_CHIP") (pin "31") (pinfunction "VSS_1_31") (pintype "power_in"))
      (node (ref "STM_CHIP") (pin "47") (pinfunction "VSS_2_47") (pintype "power_in"))
      (node (ref "STM_CHIP") (pin "63") (pinfunction "VSS_3_63") (pintype "power_in"))
      (node (ref "SYS-C1") (pin "2") (pinfunction "2_2") (pintype "passive"))
      (node (ref "SYS-C3") (pin "2") (pinfunction "2_2") (pintype "passive"))
      (node (ref "SYS-L1") (pin "2") (pinfunction "2_2") (pintype "passive"))
      (node (ref "U$4") (pin "LCD_GND") (pinfunction "LCD_GND_LCD_GND") (pintype "passive"))
      (node (ref "U2") (pin "14") (pinfunction "AGND_14") (pintype "passive"))
      (node (ref "U2") (pin "16") (pinfunction "AGND_16") (pintype "passive"))
      (node (ref "U2") (pin "19") (pinfunction "AGND_19") (pintype "passive"))
      (node (ref "U2") (pin "29") (pinfunction "GND_29") (pintype "passive"))
      (node (ref "U2") (pin "3") (pinfunction "AGND_3") (pintype "passive"))
      (node (ref "U2") (pin "48") (pinfunction "AGND_48") (pintype "passive"))
      (node (ref "U2") (pin "9") (pinfunction "AGND_9") (pintype "passive"))
      (node (ref "W5500-C1") (pin "2") (pinfunction "2_2") (pintype "passive"))
      (node (ref "W5500-C10") (pin "2") (pinfunction "2_2") (pintype "passive"))
      (node (ref "W5500-C11") (pin "2") (pinfunction "2_2") (pintype "passive"))
      (node (ref "W5500-C2") (pin "2") (pinfunction "2_2") (pintype "passive"))
      (node (ref "W5500-C3") (pin "2") (pinfunction "2_2") (pintype "passive"))
      (node (ref "W5500-C4") (pin "2") (pinfunction "2_2") (pintype "passive"))
      (node (ref "W5500-C5") (pin "2") (pinfunction "2_2") (pintype "passive"))
      (node (ref "W5500-C6") (pin "2") (pinfunction "2_2") (pintype "passive"))
      (node (ref "W5500-C7") (pin "2") (pinfunction "2_2") (pintype "passive"))
      (node (ref "W5500-C8") (pin "2") (pinfunction "2_2") (pintype "passive"))
      (node (ref "W5500-C9") (pin "2") (pinfunction "2_2") (pintype "passive"))
      (node (ref "W5500-R11") (pin "1") (pinfunction "1_1") (pintype "passive"))
      (node (ref "W5500-R4") (pin "2") (pinfunction "2_2") (pintype "passive"))
      (node (ref "W5500-R5") (pin "2") (pinfunction "2_2") (pintype "passive"))
      (node (ref "W5500-R6") (pin "2") (pinfunction "2_2") (pintype "passive"))
      (node (ref "W5500-R7") (pin "2") (pinfunction "2_2") (pintype "passive"))
      (node (ref "W5500-R8") (pin "2") (pinfunction "2_2") (pintype "passive"))
    )
    (net (code "17") (name "DHT_DATA") (class "Default")
      (node (ref "DHT-R1") (pin "2") (pinfunction "2_2") (pintype "passive"))
      (node (ref "SENSOR-DHT") (pin "2") (pinfunction "2_2") (pintype "passive"))
      (node (ref "STM_CHIP") (pin "15") (pinfunction "PA1_15") (pintype "bidirectional"))
    )
    (net (code "18") (name "ESP_GPIO0") (class "Default")
      (node (ref "ESP-GPIO0") (pin "2") (pinfunction "2_2") (pintype "passive"))
      (node (ref "ESP8266") (pin "GPIO0") (pinfunction "GPIO0_GPIO0") (pintype "bidirectional"))
    )
    (net (code "19") (name "ESP_RX") (class "Default")
      (node (ref "ESP-UART-A") (pin "2") (pinfunction "2_2") (pintype "passive"))
      (node (ref "ESP8266") (pin "URXD") (pinfunction "URXD_URXD") (pintype "bidirectional"))
      (node (ref "STM_CHIP") (pin "16") (pinfunction "PA2_16") (pintype "bidirectional"))
    )
    (net (code "20") (name "ESP_TX") (class "Default")
      (node (ref "ESP-UART-A") (pin "3") (pinfunction "3_3") (pintype "passive"))
      (node (ref "ESP8266") (pin "UTXD") (pinfunction "UTXD_UTXD") (pintype "bidirectional"))
      (node (ref "STM_CHIP") (pin "17") (pinfunction "PA3_17") (pintype "bidirectional"))
    )
    (net (code "21") (name "ETH_CS") (class "Default")
      (node (ref "STM_CHIP") (pin "33") (pinfunction "PB12_33") (pintype "bidirectional"))
      (node (ref "U2") (pin "32") (pinfunction "SCS_N_32") (pintype "passive"))
    )
    (net (code "22") (name "ETH_MISO") (class "Default")
      (node (ref "STM_CHIP") (pin "35") (pinfunction "PB14_35") (pintype "bidirectional"))
      (node (ref "U2") (pin "34") (pinfunction "MISO_34") (pintype "passive"))
    )
    (net (code "23") (name "ETH_MOSI") (class "Default")
      (node (ref "STM_CHIP") (pin "36") (pinfunction "PB15_36") (pintype "bidirectional"))
      (node (ref "U2") (pin "35") (pinfunction "MOSI_35") (pintype "passive"))
    )
    (net (code "24") (name "ETH_RSTN") (class "Default")
      (node (ref "STM_CHIP") (pin "37") (pinfunction "PC6_37") (pintype "bidirectional"))
      (node (ref "U2") (pin "37") (pinfunction "RST_N_37") (pintype "passive"))
      (node (ref "W5500-R9") (pin "1") (pinfunction "1_1") (pintype "passive"))
    )
    (net (code "25") (name "ETH_SCK") (class "Default")
      (node (ref "STM_CHIP") (pin "34") (pinfunction "PB13_34") (pintype "bidirectional"))
      (node (ref "U2") (pin "33") (pinfunction "SCLK_33") (pintype "passive"))
    )
    (net (code "26") (name "F_CS") (class "Default")
      (node (ref "STM_CHIP") (pin "29") (pinfunction "PB10_29") (pintype "bidirectional"))
      (node (ref "U$4") (pin "F_CS") (pinfunction "F_CS_F_CS") (pintype "passive"))
    )
    (net (code "27") (name "GESP") (class "Default")
      (node (ref "ESP-C1") (pin "2") (pinfunction "2_2") (pintype "passive"))
      (node (ref "ESP-GND") (pin "2") (pinfunction "2_2") (pintype "passive"))
      (node (ref "ESP-GPIO0") (pin "3") (pinfunction "3_3") (pintype "passive"))
      (node (ref "ESP8266") (pin "GND") (pinfunction "GND_GND") (pintype "bidirectional"))
      (node (ref "ESP8266") (pin "GPIO15") (pinfunction "GPIO15_GPIO15") (pintype "bidirectional"))
    )
    (net (code "28") (name "GEXT") (class "Default")
      (node (ref "ESP-GND") (pin "3") (pinfunction "3_3") (pintype "passive"))
      (node (ref "ESP-UART-A") (pin "4") (pinfunction "4_4") (pintype "passive"))
    )
    (net (code "29") (name "LCD_CS") (class "Default")
      (node (ref "STM_CHIP") (pin "20") (pinfunction "PA4_20") (pintype "bidirectional"))
      (node (ref "U$4") (pin "LCD_CS") (pinfunction "LCD_CS_LCD_CS") (pintype "passive"))
    )
    (net (code "30") (name "LCD_D{slash}C") (class "Default")
      (node (ref "STM_CHIP") (pin "24") (pinfunction "PC4_24") (pintype "bidirectional"))
      (node (ref "U$4") (pin "LCD_D/C") (pinfunction "LCD_D/C_LCD_D/C") (pintype "passive"))
    )
    (net (code "31") (name "LCD_LED") (class "Default")
      (node (ref "LCD-R1") (pin "1") (pinfunction "1_1") (pintype "passive"))
      (node (ref "U$4") (pin "LCD_LED") (pinfunction "LCD_LED_LCD_LED") (pintype "passive"))
    )
    (net (code "32") (name "LCD_MISO") (class "Default")
      (node (ref "STM_CHIP") (pin "22") (pinfunction "PA6_22") (pintype "bidirectional"))
      (node (ref "U$4") (pin "LCD_MISO") (pinfunction "LCD_MISO_LCD_MISO") (pintype "passive"))
      (node (ref "U$4") (pin "SD_MISO") (pinfunction "SD_MISO_SD_MISO") (pintype "passive"))
    )
    (net (code "33") (name "LCD_MOSI") (class "Default")
      (node (ref "STM_CHIP") (pin "23") (pinfunction "PA7_23") (pintype "bidirectional"))
      (node (ref "U$4") (pin "LCD_MOSI") (pinfunction "LCD_MOSI_LCD_MOSI") (pintype "passive"))
      (node (ref "U$4") (pin "SD_MOSI") (pinfunction "SD_MOSI_SD_MOSI") (pintype "passive"))
    )
    (net (code "34") (name "LCD_RESET") (class "Default")
      (node (ref "STM_CHIP") (pin "25") (pinfunction "PC5_25") (pintype "bidirectional"))
      (node (ref "U$4") (pin "LCD_RESET") (pinfunction "LCD_RESET_LCD_RESET") (pintype "passive"))
    )
    (net (code "35") (name "LCD_SCK") (class "Default")
      (node (ref "STM_CHIP") (pin "21") (pinfunction "PA5_21") (pintype "bidirectional"))
      (node (ref "U$4") (pin "LCD_SCK") (pinfunction "LCD_SCK_LCD_SCK") (pintype "passive"))
      (node (ref "U$4") (pin "SD_SCK") (pinfunction "SD_SCK_SD_SCK") (pintype "passive"))
    )
    (net (code "36") (name "LINKLED") (class "Default")
      (node (ref "ETH-R5") (pin "1") (pinfunction "1_1") (pintype "passive"))
      (node (ref "U2") (pin "25") (pinfunction "LINKLED_25") (pintype "passive"))
    )
    (net (code "37") (name "MQ6_DATA") (class "Default")
      (node (ref "SENSOR-MQ7") (pin "B1") (pinfunction "B1_B1") (pintype "bidirectional"))
      (node (ref "STM_CHIP") (pin "26") (pinfunction "PB0_26") (pintype "bidirectional"))
    )
    (net (code "38") (name "MQ7_DATA") (class "Default")
      (node (ref "SENSOR-MQ6") (pin "B1") (pinfunction "B1_B1") (pintype "bidirectional"))
      (node (ref "STM_CHIP") (pin "27") (pinfunction "PB1_27") (pintype "bidirectional"))
    )
    (net (code "39") (name "Net-(ADE-R1-Pad1)") (class "Default")
      (node (ref "ADE-R1") (pin "1") (pinfunction "1_1") (pintype "passive"))
      (node (ref "VAC_IN1") (pin "PWR") (pinfunction "PWR_PWR") (pintype "bidirectional"))
    )
    (net (code "40") (name "Net-(ADE-R2-Pad1)") (class "Default")
      (node (ref "ADE-R2") (pin "1") (pinfunction "1_1") (pintype "passive"))
      (node (ref "VAC_IN2") (pin "PWR") (pinfunction "PWR_PWR") (pintype "bidirectional"))
    )
    (net (code "41") (name "Net-(ADE-R3-Pad1)") (class "Default")
      (node (ref "ADE-R3") (pin "1") (pinfunction "1_1") (pintype "passive"))
      (node (ref "VAC_IN3") (pin "PWR") (pinfunction "PWR_PWR") (pintype "bidirectional"))
    )
    (net (code "42") (name "Net-(ADE-R7-Pad1)") (class "Default")
      (node (ref "ADE-R7") (pin "1") (pinfunction "1_1") (pintype "passive"))
      (node (ref "VAC_IN1") (pin "GND") (pinfunction "GND_GND") (pintype "bidirectional"))
      (node (ref "VAC_IN1") (pin "GNDBREAK") (pinfunction "GNDBREAK_GNDBREAK") (pintype "bidirectional"))
      (node (ref "VAC_IN2") (pin "GND") (pinfunction "GND_GND") (pintype "bidirectional"))
      (node (ref "VAC_IN2") (pin "GNDBREAK") (pinfunction "GNDBREAK_GNDBREAK") (pintype "bidirectional"))
      (node (ref "VAC_IN3") (pin "GND") (pinfunction "GND_GND") (pintype "bidirectional"))
      (node (ref "VAC_IN3") (pin "GNDBREAK") (pinfunction "GNDBREAK_GNDBREAK") (pintype "bidirectional"))
    )
    (net (code "43") (name "Net-(ADE-R8-Pad2)") (class "Default")
      (node (ref "ADE-R8") (pin "2") (pinfunction "2_2") (pintype "passive"))
      (node (ref "ADE-R9") (pin "1") (pinfunction "1_1") (pintype "passive"))
      (node (ref "CT1") (pin "1") (pinfunction "1_1") (pintype "passive"))
    )
    (net (code "44") (name "Net-(ADE-R10-Pad1)") (class "Default")
      (node (ref "ADE-R10") (pin "1") (pinfunction "1_1") (pintype "passive"))
      (node (ref "ADE-R8") (pin "1") (pinfunction "1_1") (pintype "passive"))
      (node (ref "CT1") (pin "2") (pinfunction "2_2") (pintype "passive"))
      (node (ref "CT1") (pin "5") (pinfunction "5_5") (pintype "passive"))
    )
    (net (code "45") (name "Net-(ADE-R11-Pad1)") (class "Default")
      (node (ref "ADE-R11") (pin "1") (pinfunction "1_1") (pintype "passive"))
      (node (ref "ADE-R13") (pin "1") (pinfunction "1_1") (pintype "passive"))
      (node (ref "CT2") (pin "2") (pinfunction "2_2") (pintype "passive"))
      (node (ref "CT2") (pin "5") (pinfunction "5_5") (pintype "passive"))
    )
    (net (code "46") (name "Net-(ADE-R11-Pad2)") (class "Default")
      (node (ref "ADE-R11") (pin "2") (pinfunction "2_2") (pintype "passive"))
      (node (ref "ADE-R12") (pin "1") (pinfunction "1_1") (pintype "passive"))
      (node (ref "CT2") (pin "1") (pinfunction "1_1") (pintype "passive"))
    )
    (net (code "47") (name "Net-(ADE-R14-Pad1)") (class "Default")
      (node (ref "ADE-R14") (pin "1") (pinfunction "1_1") (pintype "passive"))
      (node (ref "ADE-R16") (pin "1") (pinfunction "1_1") (pintype "passive"))
      (node (ref "CT3") (pin "2") (pinfunction "2_2") (pintype "passive"))
      (node (ref "CT3") (pin "5") (pinfunction "5_5") (pintype "passive"))
    )
    (net (code "48") (name "Net-(ADE-R14-Pad2)") (class "Default")
      (node (ref "ADE-R14") (pin "2") (pinfunction "2_2") (pintype "passive"))
      (node (ref "ADE-R15") (pin "1") (pinfunction "1_1") (pintype "passive"))
      (node (ref "CT3") (pin "1") (pinfunction "1_1") (pintype "passive"))
    )
    (net (code "49") (name "Net-(ETHERNET-LED1_K)") (class "Default")
      (node (ref "ETH-R4") (pin "2") (pinfunction "2_2") (pintype "passive"))
      (node (ref "ETHERNET") (pin "10") (pinfunction "LED1_K_10") (pintype "bidirectional"))
    )
    (net (code "50") (name "Net-(ETHERNET-LED2_K)") (class "Default")
      (node (ref "ETH-R5") (pin "2") (pinfunction "2_2") (pintype "passive"))
      (node (ref "ETHERNET") (pin "11") (pinfunction "LED2_K_11") (pintype "bidirectional"))
    )
    (net (code "51") (name "Net-(ETHERNET-RCT)") (class "Default")
      (node (ref "ETH-C3") (pin "2") (pinfunction "2_2") (pintype "passive"))
      (node (ref "ETH-R6") (pin "1") (pinfunction "1_1") (pintype "passive"))
      (node (ref "ETH-R7") (pin "2") (pinfunction "2_2") (pintype "passive"))
      (node (ref "ETHERNET") (pin "6") (pinfunction "RCT_6") (pintype "bidirectional"))
    )
    (net (code "52") (name "Net-(ETHERNET-RX+)") (class "Default")
      (node (ref "ETH-C2") (pin "1") (pinfunction "1_1") (pintype "passive"))
      (node (ref "ETHERNET") (pin "7") (pinfunction "RX+_7") (pintype "bidirectional"))
    )
    (net (code "53") (name "Net-(ETHERNET-RX-)") (class "Default")
      (node (ref "ETH-C4") (pin "1") (pinfunction "1_1") (pintype "passive"))
      (node (ref "ETHERNET") (pin "8") (pinfunction "RX-_8") (pintype "bidirectional"))
    )
    (net (code "54") (name "Net-(ETHERNET-TCT)") (class "Default")
      (node (ref "ETH-C1") (pin "2") (pinfunction "2_2") (pintype "passive"))
      (node (ref "ETH-R3") (pin "1") (pinfunction "1_1") (pintype "passive"))
      (node (ref "ETHERNET") (pin "3") (pinfunction "TCT_3") (pintype "bidirectional"))
    )
    (net (code "55") (name "Net-(IC1-RF_ANT)") (class "Default")
      (node (ref "IC1") (pin "P$60") (pinfunction "RF_ANT_P$60") (pintype "bidirectional"))
      (node (ref "SIM900-ANT") (pin "ANTENNA") (pinfunction "ANT_ANTENNA") (pintype "bidirectional"))
    )
    (net (code "56") (name "Net-(IC1-SIM_CLK)") (class "Default")
      (node (ref "IC1") (pin "P$32") (pinfunction "SIM_CLK_P$32") (pintype "bidirectional"))
      (node (ref "SIM900-R2") (pin "1") (pinfunction "1_1") (pintype "passive"))
    )
    (net (code "57") (name "Net-(IC1-SIM_DATA)") (class "Default")
      (node (ref "IC1") (pin "P$31") (pinfunction "SIM_DATA_P$31") (pintype "bidirectional"))
      (node (ref "SIM900-R3") (pin "1") (pinfunction "1_1") (pintype "passive"))
    )
    (net (code "58") (name "Net-(IC1-SIM_RST)") (class "Default")
      (node (ref "IC1") (pin "P$33") (pinfunction "SIM_RST_P$33") (pintype "bidirectional"))
      (node (ref "SIM900-R1") (pin "1") (pinfunction "1_1") (pintype "passive"))
    )
    (net (code "59") (name "Net-(IC1-VRTC)") (class "Default")
      (node (ref "IC1") (pin "P$26") (pinfunction "VRTC_P$26") (pintype "power_in"))
      (node (ref "SIM900-C3") (pin "1") (pinfunction "1_1") (pintype "passive"))
    )
    (net (code "60") (name "Net-(IC4A-CLKIN)") (class "Default")
      (node (ref "ADE-C3") (pin "1") (pinfunction "1_1") (pintype "passive"))
      (node (ref "ADE-XTAL") (pin "1") (pinfunction "1_1") (pintype "passive"))
      (node (ref "IC4") (pin "19") (pinfunction "CLKIN_19") (pintype "input"))
    )
    (net (code "61") (name "Net-(IC4A-CLKOUT)") (class "Default")
      (node (ref "ADE-C4") (pin "1") (pinfunction "1_1") (pintype "passive"))
      (node (ref "ADE-XTAL") (pin "2") (pinfunction "2_2") (pintype "passive"))
      (node (ref "IC4") (pin "20") (pinfunction "CLKOUT_20") (pintype "output"))
    )
    (net (code "62") (name "Net-(IC4C-IN)") (class "Default")
      (node (ref "ADE-C12") (pin "1") (pinfunction "1_1") (pintype "passive"))
      (node (ref "ADE-R10") (pin "2") (pinfunction "2_2") (pintype "passive"))
      (node (ref "IC4") (pin "6") (pinfunction "IN_6") (pintype "input"))
    )
    (net (code "63") (name "Net-(IC4C-IP)") (class "Default")
      (node (ref "ADE-C11") (pin "1") (pinfunction "1_1") (pintype "passive"))
      (node (ref "ADE-R9") (pin "2") (pinfunction "2_2") (pintype "passive"))
      (node (ref "IC4") (pin "5") (pinfunction "IP_5") (pintype "input"))
    )
    (net (code "64") (name "Net-(IC4D-IN)") (class "Default")
      (node (ref "ADE-C14") (pin "1") (pinfunction "1_1") (pintype "passive"))
      (node (ref "ADE-R13") (pin "2") (pinfunction "2_2") (pintype "passive"))
      (node (ref "IC4") (pin "8") (pinfunction "IN_8") (pintype "input"))
    )
    (net (code "65") (name "Net-(IC4D-IP)") (class "Default")
      (node (ref "ADE-C13") (pin "1") (pinfunction "1_1") (pintype "passive"))
      (node (ref "ADE-R12") (pin "2") (pinfunction "2_2") (pintype "passive"))
      (node (ref "IC4") (pin "7") (pinfunction "IP_7") (pintype "input"))
    )
    (net (code "66") (name "Net-(IC4E-IN)") (class "Default")
      (node (ref "ADE-C16") (pin "1") (pinfunction "1_1") (pintype "passive"))
      (node (ref "ADE-R16") (pin "2") (pinfunction "2_2") (pintype "passive"))
      (node (ref "IC4") (pin "10") (pinfunction "IN_10") (pintype "input"))
    )
    (net (code "67") (name "Net-(IC4E-IP)") (class "Default")
      (node (ref "ADE-C15") (pin "1") (pinfunction "1_1") (pintype "passive"))
      (node (ref "ADE-R15") (pin "2") (pinfunction "2_2") (pintype "passive"))
      (node (ref "IC4") (pin "9") (pinfunction "IP_9") (pintype "input"))
    )
    (net (code "68") (name "Net-(IC4F-REF)") (class "Default")
      (node (ref "ADE-C1") (pin "1") (pinfunction "1_1") (pintype "passive"))
      (node (ref "ADE-C2") (pin "1") (pinfunction "1_1") (pintype "passive"))
      (node (ref "IC4") (pin "12") (pinfunction "REF_12") (pintype "bidirectional"))
    )
    (net (code "69") (name "Net-(IC4G-VAP)") (class "Default")
      (node (ref "ADE-C7") (pin "1") (pinfunction "1_1") (pintype "passive"))
      (node (ref "ADE-R1") (pin "2") (pinfunction "2_2") (pintype "passive"))
      (node (ref "ADE-R4") (pin "2") (pinfunction "2_2") (pintype "passive"))
      (node (ref "IC4") (pin "16") (pinfunction "VAP_16") (pintype "input"))
    )
    (net (code "70") (name "Net-(IC4G-VBP)") (class "Default")
      (node (ref "ADE-C8") (pin "1") (pinfunction "1_1") (pintype "passive"))
      (node (ref "ADE-R2") (pin "2") (pinfunction "2_2") (pintype "passive"))
      (node (ref "ADE-R5") (pin "2") (pinfunction "2_2") (pintype "passive"))
      (node (ref "IC4") (pin "15") (pinfunction "VBP_15") (pintype "input"))
    )
    (net (code "71") (name "Net-(IC4G-VCP)") (class "Default")
      (node (ref "ADE-C9") (pin "1") (pinfunction "1_1") (pintype "passive"))
      (node (ref "ADE-R3") (pin "2") (pinfunction "2_2") (pintype "passive"))
      (node (ref "ADE-R6") (pin "2") (pinfunction "2_2") (pintype "passive"))
      (node (ref "IC4") (pin "14") (pinfunction "VCP_14") (pintype "input"))
    )
    (net (code "72") (name "Net-(IC4G-VN)") (class "Default")
      (node (ref "ADE-C10") (pin "1") (pinfunction "1_1") (pintype "passive"))
      (node (ref "ADE-R7") (pin "2") (pinfunction "2_2") (pintype "passive"))
      (node (ref "IC4") (pin "13") (pinfunction "VN_13") (pintype "input"))
    )
    (net (code "73") (name "Net-(MQ6-R1-Pad2)") (class "Default")
      (node (ref "MQ6-R1") (pin "2") (pinfunction "2_2") (pintype "passive"))
      (node (ref "SENSOR-MQ6") (pin "B2") (pinfunction "B2_B2") (pintype "bidirectional"))
    )
    (net (code "74") (name "Net-(MQ7-R1-Pad2)") (class "Default")
      (node (ref "MQ7-R1") (pin "2") (pinfunction "2_2") (pintype "passive"))
      (node (ref "SENSOR-MQ7") (pin "B2") (pinfunction "B2_B2") (pintype "bidirectional"))
    )
    (net (code "75") (name "Net-(SIM900-LED1-PadA)") (class "Default")
      (node (ref "SIM900-LED1") (pin "A") (pinfunction "A_A") (pintype "passive"))
      (node (ref "SIM900-R4") (pin "1") (pinfunction "1_1") (pintype "passive"))
    )
    (net (code "76") (name "Net-(SIM900-LED1-PadC)") (class "Default")
      (node (ref "SIM900-LED1") (pin "C") (pinfunction "C_C") (pintype "passive"))
      (node (ref "SIM900-T1") (pin "C") (pinfunction "C_C") (pintype "passive"))
    )
    (net (code "77") (name "Net-(SIM900-LED2-PadA)") (class "Default")
      (node (ref "SIM900-LED2") (pin "A") (pinfunction "A_A") (pintype "passive"))
      (node (ref "SIM900-R7") (pin "1") (pinfunction "1_1") (pintype "passive"))
    )
    (net (code "78") (name "Net-(SIM900-LED2-PadC)") (class "Default")
      (node (ref "SIM900-LED2") (pin "C") (pinfunction "C_C") (pintype "passive"))
      (node (ref "SIM900-T2") (pin "C") (pinfunction "C_C") (pintype "passive"))
    )
    (net (code "79") (name "Net-(SIM900-R5-Pad1)") (class "Default")
      (node (ref "SIM900-R5") (pin "1") (pinfunction "1_1") (pintype "passive"))
      (node (ref "SIM900-R6") (pin "1") (pinfunction "1_1") (pintype "passive"))
      (node (ref "SIM900-T1") (pin "B") (pinfunction "B_B") (pintype "passive"))
    )
    (net (code "80") (name "Net-(SIM900-R8-Pad1)") (class "Default")
      (node (ref "SIM900-R8") (pin "1") (pinfunction "1_1") (pintype "passive"))
      (node (ref "SIM900-R9") (pin "1") (pinfunction "1_1") (pintype "passive"))
      (node (ref "SIM900-T2") (pin "B") (pinfunction "B_B") (pintype "passive"))
    )
    (net (code "81") (name "Net-(SIM900-R10-Pad2)") (class "Default")
      (node (ref "SIM900-R10") (pin "2") (pinfunction "2_2") (pintype "passive"))
      (node (ref "SIM900-T3") (pin "B") (pinfunction "B_B") (pintype "passive"))
    )
    (net (code "82") (name "Net-(SIM900-R11-Pad2)") (class "Default")
      (node (ref "SIM900-R11") (pin "2") (pinfunction "2_2") (pintype "passive"))
      (node (ref "SIM900-T4") (pin "B") (pinfunction "B_B") (pintype "passive"))
    )
    (net (code "83") (name "Net-(STM-HD1-Pad2)") (class "Default")
      (node (ref "STM-HD1") (pin "2") (pinfunction "2_2") (pintype "passive"))
      (node (ref "STM-R4") (pin "2") (pinfunction "2_2") (pintype "passive"))
    )
    (net (code "84") (name "Net-(STM-HD2-Pad2)") (class "Default")
      (node (ref "STM-HD2") (pin "2") (pinfunction "2_2") (pintype "passive"))
      (node (ref "STM-R5") (pin "2") (pinfunction "2_2") (pintype "passive"))
    )
    (net (code "85") (name "Net-(STM_CHIP-PC14-OSC32_IN)") (class "Default")
      (node (ref "STM-C5") (pin "2") (pinfunction "2_2") (pintype "passive"))
      (node (ref "STM-XTAL2") (pin "1") (pinfunction "1_1") (pintype "passive"))
      (node (ref "STM_CHIP") (pin "3") (pinfunction "PC14-OSC32_IN_3") (pintype "bidirectional"))
    )
    (net (code "86") (name "Net-(STM_CHIP-PC15-OSC32_OUT)") (class "Default")
      (node (ref "STM-C6") (pin "1") (pinfunction "1_1") (pintype "passive"))
      (node (ref "STM-XTAL2") (pin "2") (pinfunction "2_2") (pintype "passive"))
      (node (ref "STM_CHIP") (pin "4") (pinfunction "PC15-OSC32_OUT_4") (pintype "bidirectional"))
    )
    (net (code "87") (name "Net-(STM_CHIP-PH0_-OSC_IN)") (class "Default")
      (node (ref "STM-C2") (pin "2") (pinfunction "2_2") (pintype "passive"))
      (node (ref "STM-XTAL1") (pin "1") (pinfunction "1_1") (pintype "passive"))
      (node (ref "STM_CHIP") (pin "5") (pinfunction "PH0_-OSC_IN_5") (pintype "bidirectional"))
    )
    (net (code "88") (name "Net-(STM_CHIP-PH1-_OSC_OUT)") (class "Default")
      (node (ref "STM-C3") (pin "1") (pinfunction "1_1") (pintype "passive"))
      (node (ref "STM-XTAL1") (pin "2") (pinfunction "2_2") (pintype "passive"))
      (node (ref "STM_CHIP") (pin "6") (pinfunction "PH1-_OSC_OUT_6") (pintype "bidirectional"))
    )
    (net (code "89") (name "Net-(U2-1V2O)") (class "Default")
      (node (ref "U2") (pin "22") (pinfunction "1V2O_22") (pintype "passive"))
      (node (ref "W5500-C4") (pin "1") (pinfunction "1_1") (pintype "passive"))
    )
    (net (code "90") (name "Net-(U2-PMODE0)") (class "Default")
      (node (ref "U2") (pin "45") (pinfunction "PMODE0_45") (pintype "passive"))
      (node (ref "W5500-R3") (pin "2") (pinfunction "2_2") (pintype "passive"))
    )
    (net (code "91") (name "Net-(U2-PMODE1)") (class "Default")
      (node (ref "U2") (pin "44") (pinfunction "PMODE1_44") (pintype "passive"))
      (node (ref "W5500-R2") (pin "2") (pinfunction "2_2") (pintype "passive"))
    )
    (net (code "92") (name "Net-(U2-PMODE2)") (class "Default")
      (node (ref "U2") (pin "43") (pinfunction "PMODE2_43") (pintype "passive"))
      (node (ref "W5500-R1") (pin "2") (pinfunction "2_2") (pintype "passive"))
    )
    (net (code "93") (name "Net-(U2-RSVD-Pad23)") (class "Default")
      (node (ref "U2") (pin "23") (pinfunction "RSVD_23") (pintype "passive"))
      (node (ref "W5500-R11") (pin "2") (pinfunction "2_2") (pintype "passive"))
    )
    (net (code "94") (name "Net-(U2-RSVD-Pad38)") (class "Default")
      (node (ref "U2") (pin "38") (pinfunction "RSVD_38") (pintype "passive"))
      (node (ref "W5500-R8") (pin "1") (pinfunction "1_1") (pintype "passive"))
    )
    (net (code "95") (name "Net-(U2-RSVD-Pad39)") (class "Default")
      (node (ref "U2") (pin "39") (pinfunction "RSVD_39") (pintype "passive"))
      (node (ref "W5500-R7") (pin "1") (pinfunction "1_1") (pintype "passive"))
    )
    (net (code "96") (name "Net-(U2-RSVD-Pad40)") (class "Default")
      (node (ref "U2") (pin "40") (pinfunction "RSVD_40") (pintype "passive"))
      (node (ref "W5500-R6") (pin "1") (pinfunction "1_1") (pintype "passive"))
    )
    (net (code "97") (name "Net-(U2-RSVD-Pad41)") (class "Default")
      (node (ref "U2") (pin "41") (pinfunction "RSVD_41") (pintype "passive"))
      (node (ref "W5500-R5") (pin "1") (pinfunction "1_1") (pintype "passive"))
    )
    (net (code "98") (name "Net-(U2-RSVD-Pad42)") (class "Default")
      (node (ref "U2") (pin "42") (pinfunction "RSVD_42") (pintype "passive"))
      (node (ref "W5500-R4") (pin "1") (pinfunction "1_1") (pintype "passive"))
    )
    (net (code "99") (name "Net-(U2-TOCAP)") (class "Default")
      (node (ref "U2") (pin "20") (pinfunction "TOCAP_20") (pintype "passive"))
      (node (ref "W5500-C3") (pin "1") (pinfunction "1_1") (pintype "passive"))
    )
    (net (code "100") (name "Net-(U2-XI{slash}CLKIN)") (class "Default")
      (node (ref "U2") (pin "30") (pinfunction "XI/CLKIN_30") (pintype "passive"))
      (node (ref "W5500-C1") (pin "1") (pinfunction "1_1") (pintype "passive"))
      (node (ref "W5500-R10") (pin "1") (pinfunction "1_1") (pintype "passive"))
      (node (ref "W5500-XTAL") (pin "1") (pinfunction "1_1") (pintype "passive"))
    )
    (net (code "101") (name "Net-(U2-XO)") (class "Default")
      (node (ref "U2") (pin "31") (pinfunction "XO_31") (pintype "passive"))
      (node (ref "W5500-C2") (pin "1") (pinfunction "1_1") (pintype "passive"))
      (node (ref "W5500-R10") (pin "2") (pinfunction "2_2") (pintype "passive"))
      (node (ref "W5500-XTAL") (pin "2") (pinfunction "2_2") (pintype "passive"))
    )
    (net (code "102") (name "Q1") (class "Default")
      (node (ref "IC2") (pin "15") (pinfunction "QA_15") (pintype "tri_state"))
      (node (ref "SR_OUT1") (pin "3") (pinfunction "3_3") (pintype "passive"))
    )
    (net (code "103") (name "Q2") (class "Default")
      (node (ref "IC2") (pin "1") (pinfunction "QB_1") (pintype "tri_state"))
      (node (ref "SR_OUT1") (pin "4") (pinfunction "4_4") (pintype "passive"))
    )
    (net (code "104") (name "Q3") (class "Default")
      (node (ref "IC2") (pin "2") (pinfunction "QC_2") (pintype "tri_state"))
      (node (ref "SR_OUT1") (pin "5") (pinfunction "5_5") (pintype "passive"))
    )
    (net (code "105") (name "Q4") (class "Default")
      (node (ref "IC2") (pin "3") (pinfunction "QD_3") (pintype "tri_state"))
      (node (ref "SR_OUT1") (pin "6") (pinfunction "6_6") (pintype "passive"))
    )
    (net (code "106") (name "Q5") (class "Default")
      (node (ref "IC2") (pin "4") (pinfunction "QE_4") (pintype "tri_state"))
      (node (ref "SR_OUT1") (pin "7") (pinfunction "7_7") (pintype "passive"))
    )
    (net (code "107") (name "Q6") (class "Default")
      (node (ref "IC2") (pin "5") (pinfunction "QF_5") (pintype "tri_state"))
      (node (ref "SR_OUT1") (pin "8") (pinfunction "8_8") (pintype "passive"))
    )
    (net (code "108") (name "Q7") (class "Default")
      (node (ref "IC2") (pin "6") (pinfunction "QG_6") (pintype "tri_state"))
      (node (ref "SR_OUT1") (pin "9") (pinfunction "9_9") (pintype "passive"))
    )
    (net (code "109") (name "Q8") (class "Default")
      (node (ref "IC2") (pin "7") (pinfunction "QH_7") (pintype "tri_state"))
      (node (ref "SR_OUT1") (pin "10") (pinfunction "10_10") (pintype "passive"))
    )
    (net (code "110") (name "Q9") (class "Default")
      (node (ref "IC3") (pin "15") (pinfunction "QA_15") (pintype "tri_state"))
      (node (ref "SR_OUT2") (pin "3") (pinfunction "3_3") (pintype "passive"))
    )
    (net (code "111") (name "Q10") (class "Default")
      (node (ref "IC3") (pin "1") (pinfunction "QB_1") (pintype "tri_state"))
      (node (ref "SR_OUT2") (pin "4") (pinfunction "4_4") (pintype "passive"))
    )
    (net (code "112") (name "Q11") (class "Default")
      (node (ref "IC3") (pin "2") (pinfunction "QC_2") (pintype "tri_state"))
      (node (ref "SR_OUT2") (pin "5") (pinfunction "5_5") (pintype "passive"))
    )
    (net (code "113") (name "Q12") (class "Default")
      (node (ref "IC3") (pin "3") (pinfunction "QD_3") (pintype "tri_state"))
      (node (ref "SR_OUT2") (pin "6") (pinfunction "6_6") (pintype "passive"))
    )
    (net (code "114") (name "Q13") (class "Default")
      (node (ref "IC3") (pin "4") (pinfunction "QE_4") (pintype "tri_state"))
      (node (ref "SR_OUT2") (pin "7") (pinfunction "7_7") (pintype "passive"))
    )
    (net (code "115") (name "Q14") (class "Default")
      (node (ref "IC3") (pin "5") (pinfunction "QF_5") (pintype "tri_state"))
      (node (ref "SR_OUT2") (pin "8") (pinfunction "8_8") (pintype "passive"))
    )
    (net (code "116") (name "Q15") (class "Default")
      (node (ref "IC3") (pin "6") (pinfunction "QG_6") (pintype "tri_state"))
      (node (ref "SR_OUT2") (pin "9") (pinfunction "9_9") (pintype "passive"))
    )
    (net (code "117") (name "Q16") (class "Default")
      (node (ref "IC3") (pin "7") (pinfunction "QH_7") (pintype "tri_state"))
      (node (ref "SR_OUT2") (pin "10") (pinfunction "10_10") (pintype "passive"))
    )
    (net (code "118") (name "QS") (class "Default")
      (node (ref "IC2") (pin "9") (pinfunction "QH*_9") (pintype "tri_state"))
      (node (ref "IC3") (pin "14") (pinfunction "SER_14") (pintype "input"))
    )
    (net (code "119") (name "RXN") (class "Default")
      (node (ref "ETH-C4") (pin "2") (pinfunction "2_2") (pintype "passive"))
      (node (ref "ETH-R7") (pin "1") (pinfunction "1_1") (pintype "passive"))
      (node (ref "U2") (pin "5") (pinfunction "RXN_5") (pintype "passive"))
    )
    (net (code "120") (name "RXP") (class "Default")
      (node (ref "ETH-C2") (pin "2") (pinfunction "2_2") (pintype "passive"))
      (node (ref "ETH-R6") (pin "2") (pinfunction "2_2") (pintype "passive"))
      (node (ref "U2") (pin "6") (pinfunction "RXP_6") (pintype "passive"))
    )
    (net (code "121") (name "SD_CS") (class "Default")
      (node (ref "STM_CHIP") (pin "53") (pinfunction "PC12_53") (pintype "bidirectional"))
      (node (ref "U$4") (pin "SD_CS") (pinfunction "SD_CS_SD_CS") (pintype "passive"))
    )
    (net (code "122") (name "SERIAL_RX") (class "Default")
      (node (ref "STM-USART") (pin "3") (pinfunction "3_3") (pintype "passive"))
      (node (ref "STM_CHIP") (pin "43") (pinfunction "PA10_43") (pintype "bidirectional"))
    )
    (net (code "123") (name "SERIAL_TX") (class "Default")
      (node (ref "STM-USART") (pin "2") (pinfunction "2_2") (pintype "passive"))
      (node (ref "STM_CHIP") (pin "42") (pinfunction "PA9_42") (pintype "bidirectional"))
    )
    (net (code "124") (name "SIM900_PWRKEY") (class "Default")
      (node (ref "IC1") (pin "P$1") (pinfunction "PWRKEY_P$1") (pintype "power_in"))
      (node (ref "SIM900-T3") (pin "C") (pinfunction "C_C") (pintype "passive"))
    )
    (net (code "125") (name "SIM900_RESET") (class "Default")
      (node (ref "IC1") (pin "P$16") (pinfunction "NRESET_P$16") (pintype "bidirectional"))
      (node (ref "SIM900-T4") (pin "C") (pinfunction "C_C") (pintype "passive"))
    )
    (net (code "126") (name "SIM_NETLIGHT") (class "Default")
      (node (ref "IC1") (pin "P$52") (pinfunction "NETLIGHT_P$52") (pintype "bidirectional"))
      (node (ref "SIM900-R8") (pin "2") (pinfunction "2_2") (pintype "passive"))
    )
    (net (code "127") (name "SIM_PWRKEY") (class "Default")
      (node (ref "SIM900-R10") (pin "1") (pinfunction "1_1") (pintype "passive"))
      (node (ref "STM_CHIP") (pin "40") (pinfunction "PC9_40") (pintype "bidirectional"))
    )
    (net (code "128") (name "SIM_RESET") (class "Default")
      (node (ref "SIM900-R11") (pin "1") (pinfunction "1_1") (pintype "passive"))
      (node (ref "STM_CHIP") (pin "50") (pinfunction "PA15_50") (pintype "bidirectional"))
    )
    (net (code "129") (name "SIM_RX") (class "Default")
      (node (ref "IC1") (pin "P$10") (pinfunction "RXD_P$10") (pintype "input"))
      (node (ref "STM_CHIP") (pin "51") (pinfunction "PC10_51") (pintype "bidirectional"))
    )
    (net (code "130") (name "SIM_STATUS") (class "Default")
      (node (ref "IC1") (pin "P$66") (pinfunction "STATUS_P$66") (pintype "bidirectional"))
      (node (ref "SIM900-R5") (pin "2") (pinfunction "2_2") (pintype "passive"))
    )
    (net (code "131") (name "SIM_TX") (class "Default")
      (node (ref "IC1") (pin "P$9") (pinfunction "TXD_P$9") (pintype "output"))
      (node (ref "STM_CHIP") (pin "52") (pinfunction "PC11_52") (pintype "bidirectional"))
    )
    (net (code "132") (name "SR_DS") (class "Default")
      (node (ref "IC2") (pin "14") (pinfunction "SER_14") (pintype "input"))
      (node (ref "STM_CHIP") (pin "8") (pinfunction "PC0_8") (pintype "bidirectional"))
    )
    (net (code "133") (name "SR_RST") (class "Default")
      (node (ref "IC2") (pin "10") (pinfunction "SCL_10") (pintype "input"))
      (node (ref "IC3") (pin "10") (pinfunction "SCL_10") (pintype "input"))
      (node (ref "STM_CHIP") (pin "11") (pinfunction "PC3_11") (pintype "bidirectional"))
    )
    (net (code "134") (name "SR_SHCP") (class "Default")
      (node (ref "IC2") (pin "11") (pinfunction "SCK_11") (pintype "input"))
      (node (ref "IC3") (pin "11") (pinfunction "SCK_11") (pintype "input"))
      (node (ref "STM_CHIP") (pin "10") (pinfunction "PC2_10") (pintype "bidirectional"))
    )
    (net (code "135") (name "SR_STCP") (class "Default")
      (node (ref "IC2") (pin "12") (pinfunction "RCK_12") (pintype "input"))
      (node (ref "IC3") (pin "12") (pinfunction "RCK_12") (pintype "input"))
      (node (ref "STM_CHIP") (pin "9") (pinfunction "PC1_9") (pintype "bidirectional"))
    )
    (net (code "136") (name "SWD_NRST") (class "Default")
      (node (ref "PB-SWD-NRST") (pin "1") (pinfunction "1_1") (pintype "passive"))
      (node (ref "STM-C8") (pin "1") (pinfunction "1_1") (pintype "passive"))
      (node (ref "STM-SWD") (pin "5") (pinfunction "5_5") (pintype "passive"))
      (node (ref "STM_CHIP") (pin "7") (pinfunction "NRST_7") (pintype "bidirectional"))
    )
    (net (code "137") (name "SWD_SWO") (class "Default")
      (node (ref "STM-SWD") (pin "6") (pinfunction "6_6") (pintype "passive"))
      (node (ref "STM-USART") (pin "4") (pinfunction "4_4") (pintype "passive"))
      (node (ref "STM_CHIP") (pin "55") (pinfunction "PB3_55") (pintype "bidirectional"))
    )
    (net (code "138") (name "SWD_TCK") (class "Default")
      (node (ref "STM-SWD") (pin "2") (pinfunction "2_2") (pintype "passive"))
      (node (ref "STM_CHIP") (pin "49") (pinfunction "PA14_49") (pintype "bidirectional"))
    )
    (net (code "139") (name "SWD_TMS") (class "Default")
      (node (ref "STM-SWD") (pin "4") (pinfunction "4_4") (pintype "passive"))
      (node (ref "STM_CHIP") (pin "46") (pinfunction "PA13_46") (pintype "bidirectional"))
    )
    (net (code "140") (name "TXN") (class "Default")
      (node (ref "ETH-R2") (pin "1") (pinfunction "1_1") (pintype "passive"))
      (node (ref "ETHERNET") (pin "2") (pinfunction "TX-_2") (pintype "bidirectional"))
      (node (ref "U2") (pin "1") (pinfunction "TXN_1") (pintype "passive"))
    )
    (net (code "141") (name "TXP") (class "Default")
      (node (ref "ETH-R1") (pin "1") (pinfunction "1_1") (pintype "passive"))
      (node (ref "ETHERNET") (pin "1") (pinfunction "TX+_1") (pintype "bidirectional"))
      (node (ref "U2") (pin "2") (pinfunction "TXP_2") (pintype "passive"))
    )
    (net (code "142") (name "USIM_CLK") (class "Default")
      (node (ref "SIM900-R2") (pin "2") (pinfunction "2_2") (pintype "passive"))
      (node (ref "SIM_HOLDER") (pin "3") (pinfunction "CLK_3") (pintype "bidirectional"))
    )
    (net (code "143") (name "USIM_DATA") (class "Default")
      (node (ref "SIM900-R3") (pin "2") (pinfunction "2_2") (pintype "passive"))
      (node (ref "SIM_HOLDER") (pin "4") (pinfunction "I/O_4") (pintype "bidirectional"))
    )
    (net (code "144") (name "USIM_RESET") (class "Default")
      (node (ref "SIM900-R1") (pin "2") (pinfunction "2_2") (pintype "passive"))
      (node (ref "SIM_HOLDER") (pin "2") (pinfunction "RST_2") (pintype "bidirectional"))
    )
    (net (code "145") (name "USIM_VCC") (class "Default")
      (node (ref "IC1") (pin "P$30") (pinfunction "SIM_VDD_P$30") (pintype "power_in"))
      (node (ref "SIM900-C4") (pin "1") (pinfunction "1_1") (pintype "passive"))
      (node (ref "SIM900-C5") (pin "1") (pinfunction "1_1") (pintype "passive"))
      (node (ref "SIM_C1") (pin "2") (pinfunction "2_2") (pintype "passive"))
      (node (ref "SIM_C2") (pin "2") (pinfunction "2_2") (pintype "passive"))
      (node (ref "SIM_HOLDER") (pin "1") (pinfunction "VCC_1") (pintype "bidirectional"))
    )
    (net (code "146") (name "VCC") (class "Default")
      (node (ref "ETH-R1") (pin "2") (pinfunction "2_2") (pintype "passive"))
      (node (ref "ETH-R2") (pin "2") (pinfunction "2_2") (pintype "passive"))
      (node (ref "ETH-R3") (pin "2") (pinfunction "2_2") (pintype "passive"))
      (node (ref "STM-C9") (pin "1") (pinfunction "1_1") (pintype "passive"))
      (node (ref "STM-L1") (pin "2") (pinfunction "2_2") (pintype "passive"))
      (node (ref "STM_CHIP") (pin "13") (pinfunction "VDDA_13") (pintype "power_in"))
      (node (ref "SYS-C4") (pin "1") (pinfunction "1_1") (pintype "passive"))
      (node (ref "SYS-R2") (pin "2") (pinfunction "2_2") (pintype "passive"))
      (node (ref "U2") (pin "11") (pinfunction "AVDD_11") (pintype "passive"))
      (node (ref "U2") (pin "15") (pinfunction "AVDD_15") (pintype "passive"))
      (node (ref "U2") (pin "17") (pinfunction "AVDD_17") (pintype "passive"))
      (node (ref "U2") (pin "21") (pinfunction "AVDD_21") (pintype "passive"))
      (node (ref "U2") (pin "4") (pinfunction "AVDD_4") (pintype "passive"))
      (node (ref "U2") (pin "8") (pinfunction "AVDD_8") (pintype "passive"))
      (node (ref "W5500-C10") (pin "1") (pinfunction "1_1") (pintype "passive"))
      (node (ref "W5500-C11") (pin "1") (pinfunction "1_1") (pintype "passive"))
      (node (ref "W5500-C6") (pin "1") (pinfunction "1_1") (pintype "passive"))
      (node (ref "W5500-C7") (pin "1") (pinfunction "1_1") (pintype "passive"))
      (node (ref "W5500-C8") (pin "1") (pinfunction "1_1") (pintype "passive"))
      (node (ref "W5500-C9") (pin "1") (pinfunction "1_1") (pintype "passive"))
    )
    (net (code "147") (name "VDD") (class "Default")
      (node (ref "DCDC-3.5V") (pin "OUTP#1") (pinfunction "VOUT_OUTP#1") (pintype "bidirectional"))
      (node (ref "DCDC-3.5V") (pin "OUTP#2") (pinfunction "VOUT_OUTP#2") (pintype "bidirectional"))
      (node (ref "DHT-R1") (pin "1") (pinfunction "1_1") (pintype "passive"))
      (node (ref "ESP-VDD") (pin "1") (pinfunction "1_1") (pintype "passive"))
      (node (ref "ETHERNET") (pin "12") (pinfunction "LED2_A_12") (pintype "bidirectional"))
      (node (ref "ETHERNET") (pin "9") (pinfunction "LED1_A_9") (pintype "bidirectional"))
      (node (ref "IC1") (pin "P$55") (pinfunction "VBAT1_P$55") (pintype "power_in"))
      (node (ref "IC1") (pin "P$56") (pinfunction "VBAT2_P$56") (pintype "power_in"))
      (node (ref "IC1") (pin "P$57") (pinfunction "VBAT3_P$57") (pintype "power_in"))
      (node (ref "IC2") (pin "16") (pinfunction "VCC_16") (pintype "power_in"))
      (node (ref "IC3") (pin "16") (pinfunction "VCC_16") (pintype "power_in"))
      (node (ref "LCD-R1") (pin "2") (pinfunction "2_2") (pintype "passive"))
      (node (ref "SENSOR-DHT") (pin "1") (pinfunction "1_1") (pintype "passive"))
      (node (ref "SIM900-C1") (pin "+") (pinfunction "+_+") (pintype "passive"))
      (node (ref "SIM900-C2") (pin "+") (pinfunction "+_+") (pintype "passive"))
      (node (ref "SIM900-R4") (pin "2") (pinfunction "2_2") (pintype "passive"))
      (node (ref "SIM900-R7") (pin "2") (pinfunction "2_2") (pintype "passive"))
      (node (ref "STM-C1") (pin "2") (pinfunction "2_2") (pintype "passive"))
      (node (ref "STM-C10") (pin "1") (pinfunction "1_1") (pintype "passive"))
      (node (ref "STM-C11") (pin "1") (pinfunction "1_1") (pintype "passive"))
      (node (ref "STM-C12") (pin "1") (pinfunction "1_1") (pintype "passive"))
      (node (ref "STM-C13") (pin "1") (pinfunction "1_1") (pintype "passive"))
      (node (ref "STM-HD1") (pin "1") (pinfunction "1_1") (pintype "passive"))
      (node (ref "STM-HD2") (pin "1") (pinfunction "1_1") (pintype "passive"))
      (node (ref "STM-L1") (pin "1") (pinfunction "1_1") (pintype "passive"))
      (node (ref "STM-SWD") (pin "1") (pinfunction "1_1") (pintype "passive"))
      (node (ref "STM-USART") (pin "1") (pinfunction "1_1") (pintype "passive"))
      (node (ref "STM_CHIP") (pin "1") (pinfunction "VLCD_1") (pintype "power_in"))
      (node (ref "STM_CHIP") (pin "19") (pinfunction "VDD_4_19") (pintype "power_in"))
      (node (ref "STM_CHIP") (pin "32") (pinfunction "VDD_1_32") (pintype "power_in"))
      (node (ref "STM_CHIP") (pin "48") (pinfunction "VDD_2_48") (pintype "power_in"))
      (node (ref "STM_CHIP") (pin "64") (pinfunction "VDD_3_64") (pintype "power_in"))
      (node (ref "SYS-C3") (pin "1") (pinfunction "1_1") (pintype "passive"))
      (node (ref "SYS-R2") (pin "1") (pinfunction "1_1") (pintype "passive"))
      (node (ref "U$4") (pin "LCD_VCC") (pinfunction "LCD_VCC_LCD_VCC") (pintype "passive"))
      (node (ref "U2") (pin "28") (pinfunction "VDD_28") (pintype "passive"))
      (node (ref "W5500-C5") (pin "1") (pinfunction "1_1") (pintype "passive"))
      (node (ref "W5500-R1") (pin "1") (pinfunction "1_1") (pintype "passive"))
      (node (ref "W5500-R2") (pin "1") (pinfunction "1_1") (pintype "passive"))
      (node (ref "W5500-R3") (pin "1") (pinfunction "1_1") (pintype "passive"))
      (node (ref "W5500-R9") (pin "2") (pinfunction "2_2") (pintype "passive"))
    )
    (net (code "148") (name "VESP") (class "Default")
      (node (ref "ESP-C1") (pin "1") (pinfunction "1_1") (pintype "passive"))
      (node (ref "ESP-GPIO0") (pin "1") (pinfunction "1_1") (pintype "passive"))
      (node (ref "ESP-VDD") (pin "2") (pinfunction "2_2") (pintype "passive"))
      (node (ref "ESP8266") (pin "CH_PD") (pinfunction "CH_PD_CH_PD") (pintype "bidirectional"))
      (node (ref "ESP8266") (pin "VCC") (pinfunction "VCC_VCC") (pintype "bidirectional"))
    )
    (net (code "149") (name "VEXT") (class "Default")
      (node (ref "ESP-UART-A") (pin "1") (pinfunction "1_1") (pintype "passive"))
      (node (ref "ESP-VDD") (pin "3") (pinfunction "3_3") (pintype "passive"))
    )
    (net (code "150") (name "unconnected-(CT1-Pad3)") (class "Default")
      (node (ref "CT1") (pin "3") (pinfunction "3_3") (pintype "passive"))
    )
    (net (code "151") (name "unconnected-(CT1-Pad4)") (class "Default")
      (node (ref "CT1") (pin "4") (pinfunction "4_4") (pintype "passive"))
    )
    (net (code "152") (name "unconnected-(CT2-Pad3)") (class "Default")
      (node (ref "CT2") (pin "3") (pinfunction "3_3") (pintype "passive"))
    )
    (net (code "153") (name "unconnected-(CT2-Pad4)") (class "Default")
      (node (ref "CT2") (pin "4") (pinfunction "4_4") (pintype "passive"))
    )
    (net (code "154") (name "unconnected-(CT3-Pad3)") (class "Default")
      (node (ref "CT3") (pin "3") (pinfunction "3_3") (pintype "passive"))
    )
    (net (code "155") (name "unconnected-(CT3-Pad4)") (class "Default")
      (node (ref "CT3") (pin "4") (pinfunction "4_4") (pintype "passive"))
    )
    (net (code "156") (name "unconnected-(ESP8266-PadGPIO2)") (class "Default")
      (node (ref "ESP8266") (pin "GPIO2") (pinfunction "GPIO2_GPIO2") (pintype "bidirectional"))
    )
    (net (code "157") (name "unconnected-(ESP8266-PadGPIO11)") (class "Default")
      (node (ref "ESP8266") (pin "GPIO11") (pinfunction "GPIO11_GPIO11") (pintype "bidirectional"))
    )
    (net (code "158") (name "unconnected-(ESP8266-PadGPIO12)") (class "Default")
      (node (ref "ESP8266") (pin "GPIO12") (pinfunction "GPIO12_GPIO12") (pintype "bidirectional"))
    )
    (net (code "159") (name "unconnected-(ESP8266-PadGPIO13)") (class "Default")
      (node (ref "ESP8266") (pin "GPIO13") (pinfunction "GPIO13_GPIO13") (pintype "bidirectional"))
    )
    (net (code "160") (name "unconnected-(ESP8266-PadGPIO16)") (class "Default")
      (node (ref "ESP8266") (pin "GPIO16") (pinfunction "GPIO16_GPIO16") (pintype "bidirectional"))
    )
    (net (code "161") (name "unconnected-(ESP8266-PadNC)") (class "Default")
      (node (ref "ESP8266") (pin "NC") (pinfunction "NC_NC") (pintype "bidirectional"))
    )
    (net (code "162") (name "unconnected-(ESP8266-WIFI_ANT-PadANT)") (class "Default")
      (node (ref "ESP8266") (pin "ANT") (pinfunction "WIFI_ANT_ANT") (pintype "bidirectional"))
    )
    (net (code "163") (name "unconnected-(IC1-ADC-PadP$25)") (class "Default")
      (node (ref "IC1") (pin "P$25") (pinfunction "ADC_P$25") (pintype "bidirectional"))
    )
    (net (code "164") (name "unconnected-(IC1-CTS-PadP$7)") (class "Default")
      (node (ref "IC1") (pin "P$7") (pinfunction "CTS_P$7") (pintype "output"))
    )
    (net (code "165") (name "unconnected-(IC1-DBG_RXD-PadP$28)") (class "Default")
      (node (ref "IC1") (pin "P$28") (pinfunction "DBG_RXD_P$28") (pintype "input"))
    )
    (net (code "166") (name "unconnected-(IC1-DBG_TXD-PadP$27)") (class "Default")
      (node (ref "IC1") (pin "P$27") (pinfunction "DBG_TXD_P$27") (pintype "output"))
    )
    (net (code "167") (name "unconnected-(IC1-DCD-PadP$5)") (class "Default")
      (node (ref "IC1") (pin "P$5") (pinfunction "DCD_P$5") (pintype "output"))
    )
    (net (code "168") (name "unconnected-(IC1-DISP_CLK-PadP$11)") (class "Default")
      (node (ref "IC1") (pin "P$11") (pinfunction "DISP_CLK_P$11") (pintype "bidirectional"))
    )
    (net (code "169") (name "unconnected-(IC1-DISP_CS-PadP$14)") (class "Default")
      (node (ref "IC1") (pin "P$14") (pinfunction "DISP_CS_P$14") (pintype "bidirectional"))
    )
    (net (code "170") (name "unconnected-(IC1-DISP_DATA-PadP$12)") (class "Default")
      (node (ref "IC1") (pin "P$12") (pinfunction "DISP_DATA_P$12") (pintype "bidirectional"))
    )
    (net (code "171") (name "unconnected-(IC1-DISP_DC-PadP$13)") (class "Default")
      (node (ref "IC1") (pin "P$13") (pinfunction "DISP_DC_P$13") (pintype "bidirectional"))
    )
    (net (code "172") (name "unconnected-(IC1-DTR-PadP$3)") (class "Default")
      (node (ref "IC1") (pin "P$3") (pinfunction "DTR_P$3") (pintype "input"))
    )
    (net (code "173") (name "unconnected-(IC1-GPIO1{slash}KBR4-PadP$40)") (class "Default")
      (node (ref "IC1") (pin "P$40") (pinfunction "GPIO1/KBR4_P$40") (pintype "bidirectional"))
    )
    (net (code "174") (name "unconnected-(IC1-GPIO2{slash}KBR3-PadP$41)") (class "Default")
      (node (ref "IC1") (pin "P$41") (pinfunction "GPIO2/KBR3_P$41") (pintype "bidirectional"))
    )
    (net (code "175") (name "unconnected-(IC1-GPIO3{slash}KBR2-PadP$42)") (class "Default")
      (node (ref "IC1") (pin "P$42") (pinfunction "GPIO3/KBR2_P$42") (pintype "bidirectional"))
    )
    (net (code "176") (name "unconnected-(IC1-GPIO4{slash}KBR1-PadP$43)") (class "Default")
      (node (ref "IC1") (pin "P$43") (pinfunction "GPIO4/KBR1_P$43") (pintype "bidirectional"))
    )
    (net (code "177") (name "unconnected-(IC1-GPIO5{slash}KBR0-PadP$44)") (class "Default")
      (node (ref "IC1") (pin "P$44") (pinfunction "GPIO5/KBR0_P$44") (pintype "bidirectional"))
    )
    (net (code "178") (name "unconnected-(IC1-GPIO6{slash}KBC4-PadP$47)") (class "Default")
      (node (ref "IC1") (pin "P$47") (pinfunction "GPIO6/KBC4_P$47") (pintype "bidirectional"))
    )
    (net (code "179") (name "unconnected-(IC1-GPIO7{slash}KBC3-PadP$48)") (class "Default")
      (node (ref "IC1") (pin "P$48") (pinfunction "GPIO7/KBC3_P$48") (pintype "bidirectional"))
    )
    (net (code "180") (name "unconnected-(IC1-GPIO8{slash}KBC2-PadP$49)") (class "Default")
      (node (ref "IC1") (pin "P$49") (pinfunction "GPIO8/KBC2_P$49") (pintype "bidirectional"))
    )
    (net (code "181") (name "unconnected-(IC1-GPIO9{slash}KBC1-PadP$50)") (class "Default")
      (node (ref "IC1") (pin "P$50") (pinfunction "GPIO9/KBC1_P$50") (pintype "bidirectional"))
    )
    (net (code "182") (name "unconnected-(IC1-GPIO10-PadP$51)") (class "Default")
      (node (ref "IC1") (pin "P$51") (pinfunction "GPIO10_P$51") (pintype "bidirectional"))
    )
    (net (code "183") (name "unconnected-(IC1-LINEIN_L-PadP$24)") (class "Default")
      (node (ref "IC1") (pin "P$24") (pinfunction "LINEIN_L_P$24") (pintype "bidirectional"))
    )
    (net (code "184") (name "unconnected-(IC1-LINEIN_R-PadP$23)") (class "Default")
      (node (ref "IC1") (pin "P$23") (pinfunction "LINEIN_R_P$23") (pintype "bidirectional"))
    )
    (net (code "185") (name "unconnected-(IC1-MIC_N-PadP$20)") (class "Default")
      (node (ref "IC1") (pin "P$20") (pinfunction "MIC_N_P$20") (pintype "bidirectional"))
    )
    (net (code "186") (name "unconnected-(IC1-MIC_P-PadP$19)") (class "Default")
      (node (ref "IC1") (pin "P$19") (pinfunction "MIC_P_P$19") (pintype "bidirectional"))
    )
    (net (code "187") (name "unconnected-(IC1-NC-PadP$2)") (class "Default")
      (node (ref "IC1") (pin "P$2") (pinfunction "NC_P$2") (pintype "no_connect"))
    )
    (net (code "188") (name "unconnected-(IC1-NC-PadP$6)") (class "Default")
      (node (ref "IC1") (pin "P$6") (pinfunction "NC_P$6") (pintype "no_connect"))
    )
    (net (code "189") (name "unconnected-(IC1-PWM1-PadP$35)") (class "Default")
      (node (ref "IC1") (pin "P$35") (pinfunction "PWM1_P$35") (pintype "bidirectional"))
    )
    (net (code "190") (name "unconnected-(IC1-PWM2-PadP$36)") (class "Default")
      (node (ref "IC1") (pin "P$36") (pinfunction "PWM2_P$36") (pintype "bidirectional"))
    )
    (net (code "191") (name "unconnected-(IC1-RI-PadP$4)") (class "Default")
      (node (ref "IC1") (pin "P$4") (pinfunction "RI_P$4") (pintype "output"))
    )
    (net (code "192") (name "unconnected-(IC1-RTS-PadP$8)") (class "Default")
      (node (ref "IC1") (pin "P$8") (pinfunction "RTS_P$8") (pintype "input"))
    )
    (net (code "193") (name "unconnected-(IC1-SCL-PadP$38)") (class "Default")
      (node (ref "IC1") (pin "P$38") (pinfunction "SCL_P$38") (pintype "bidirectional"))
    )
    (net (code "194") (name "unconnected-(IC1-SDA-PadP$37)") (class "Default")
      (node (ref "IC1") (pin "P$37") (pinfunction "SDA_P$37") (pintype "bidirectional"))
    )
    (net (code "195") (name "unconnected-(IC1-SIM_PRESENCE-PadP$34)") (class "Default")
      (node (ref "IC1") (pin "P$34") (pinfunction "SIM_PRESENCE_P$34") (pintype "bidirectional"))
    )
    (net (code "196") (name "unconnected-(IC1-SPK_N-PadP$22)") (class "Default")
      (node (ref "IC1") (pin "P$22") (pinfunction "SPK_N_P$22") (pintype "bidirectional"))
    )
    (net (code "197") (name "unconnected-(IC1-SPK_P-PadP$21)") (class "Default")
      (node (ref "IC1") (pin "P$21") (pinfunction "SPK_P_P$21") (pintype "bidirectional"))
    )
    (net (code "198") (name "unconnected-(IC1-VDD_EXT-PadP$15)") (class "Default")
      (node (ref "IC1") (pin "P$15") (pinfunction "VDD_EXT_P$15") (pintype "bidirectional"))
    )
    (net (code "199") (name "unconnected-(IC3A-QH*-Pad9)") (class "Default")
      (node (ref "IC3") (pin "9") (pinfunction "QH*_9") (pintype "tri_state"))
    )
    (net (code "200") (name "unconnected-(SENSOR-DHT-Pad3)") (class "Default")
      (node (ref "SENSOR-DHT") (pin "3") (pinfunction "3_3") (pintype "passive"))
    )
    (net (code "201") (name "unconnected-(SIM_HOLDER-VPP-Pad5)") (class "Default")
      (node (ref "SIM_HOLDER") (pin "5") (pinfunction "VPP_5") (pintype "bidirectional"))
    )
    (net (code "202") (name "unconnected-(STM_CHIP-PA0-WKUP1-Pad14)") (class "Default")
      (node (ref "STM_CHIP") (pin "14") (pinfunction "PA0-WKUP1_14") (pintype "bidirectional"))
    )
    (net (code "203") (name "unconnected-(STM_CHIP-PA8-Pad41)") (class "Default")
      (node (ref "STM_CHIP") (pin "41") (pinfunction "PA8_41") (pintype "bidirectional"))
    )
    (net (code "204") (name "unconnected-(STM_CHIP-PA11-Pad44)") (class "Default")
      (node (ref "STM_CHIP") (pin "44") (pinfunction "PA11_44") (pintype "bidirectional"))
    )
    (net (code "205") (name "unconnected-(STM_CHIP-PA12-Pad45)") (class "Default")
      (node (ref "STM_CHIP") (pin "45") (pinfunction "PA12_45") (pintype "bidirectional"))
    )
    (net (code "206") (name "unconnected-(STM_CHIP-PB11-Pad30)") (class "Default")
      (node (ref "STM_CHIP") (pin "30") (pinfunction "PB11_30") (pintype "bidirectional"))
    )
    (net (code "207") (name "unconnected-(STM_CHIP-PC7-Pad38)") (class "Default")
      (node (ref "STM_CHIP") (pin "38") (pinfunction "PC7_38") (pintype "bidirectional"))
    )
    (net (code "208") (name "unconnected-(STM_CHIP-PC8-Pad39)") (class "Default")
      (node (ref "STM_CHIP") (pin "39") (pinfunction "PC8_39") (pintype "bidirectional"))
    )
    (net (code "209") (name "unconnected-(STM_CHIP-PC13-RTC_AF1-WKUP2-Pad2)") (class "Default")
      (node (ref "STM_CHIP") (pin "2") (pinfunction "PC13-RTC_AF1-WKUP2_2") (pintype "bidirectional"))
    )
    (net (code "210") (name "unconnected-(U2-DNC-Pad7)") (class "Default")
      (node (ref "U2") (pin "7") (pinfunction "DNC_7") (pintype "passive"))
    )
    (net (code "211") (name "unconnected-(U2-DUPLED-Pad26)") (class "Default")
      (node (ref "U2") (pin "26") (pinfunction "DUPLED_26") (pintype "passive"))
    )
    (net (code "212") (name "unconnected-(U2-EXRES1-Pad10)") (class "Default")
      (node (ref "U2") (pin "10") (pinfunction "EXRES1_10") (pintype "passive"))
    )
    (net (code "213") (name "unconnected-(U2-INT_N-Pad36)") (class "Default")
      (node (ref "U2") (pin "36") (pinfunction "INT_N_36") (pintype "passive"))
    )
    (net (code "214") (name "unconnected-(U2-NC-Pad12)") (class "Default")
      (node (ref "U2") (pin "12") (pinfunction "NC_12") (pintype "passive"))
    )
    (net (code "215") (name "unconnected-(U2-NC-Pad13)") (class "Default")
      (node (ref "U2") (pin "13") (pinfunction "NC_13") (pintype "passive"))
    )
    (net (code "216") (name "unconnected-(U2-NC-Pad46)") (class "Default")
      (node (ref "U2") (pin "46") (pinfunction "NC_46") (pintype "passive"))
    )
    (net (code "217") (name "unconnected-(U2-NC-Pad47)") (class "Default")
      (node (ref "U2") (pin "47") (pinfunction "NC_47") (pintype "passive"))
    )
    (net (code "218") (name "unconnected-(U2-SPDLED-Pad24)") (class "Default")
      (node (ref "U2") (pin "24") (pinfunction "SPDLED_24") (pintype "passive"))
    )
    (net (code "219") (name "unconnected-(U2-VBG-Pad18)") (class "Default")
      (node (ref "U2") (pin "18") (pinfunction "VBG_18") (pintype "passive"))
    )
  )
)
